# P1.net
KiCad netlist of a schematic drawn in Altium Designer
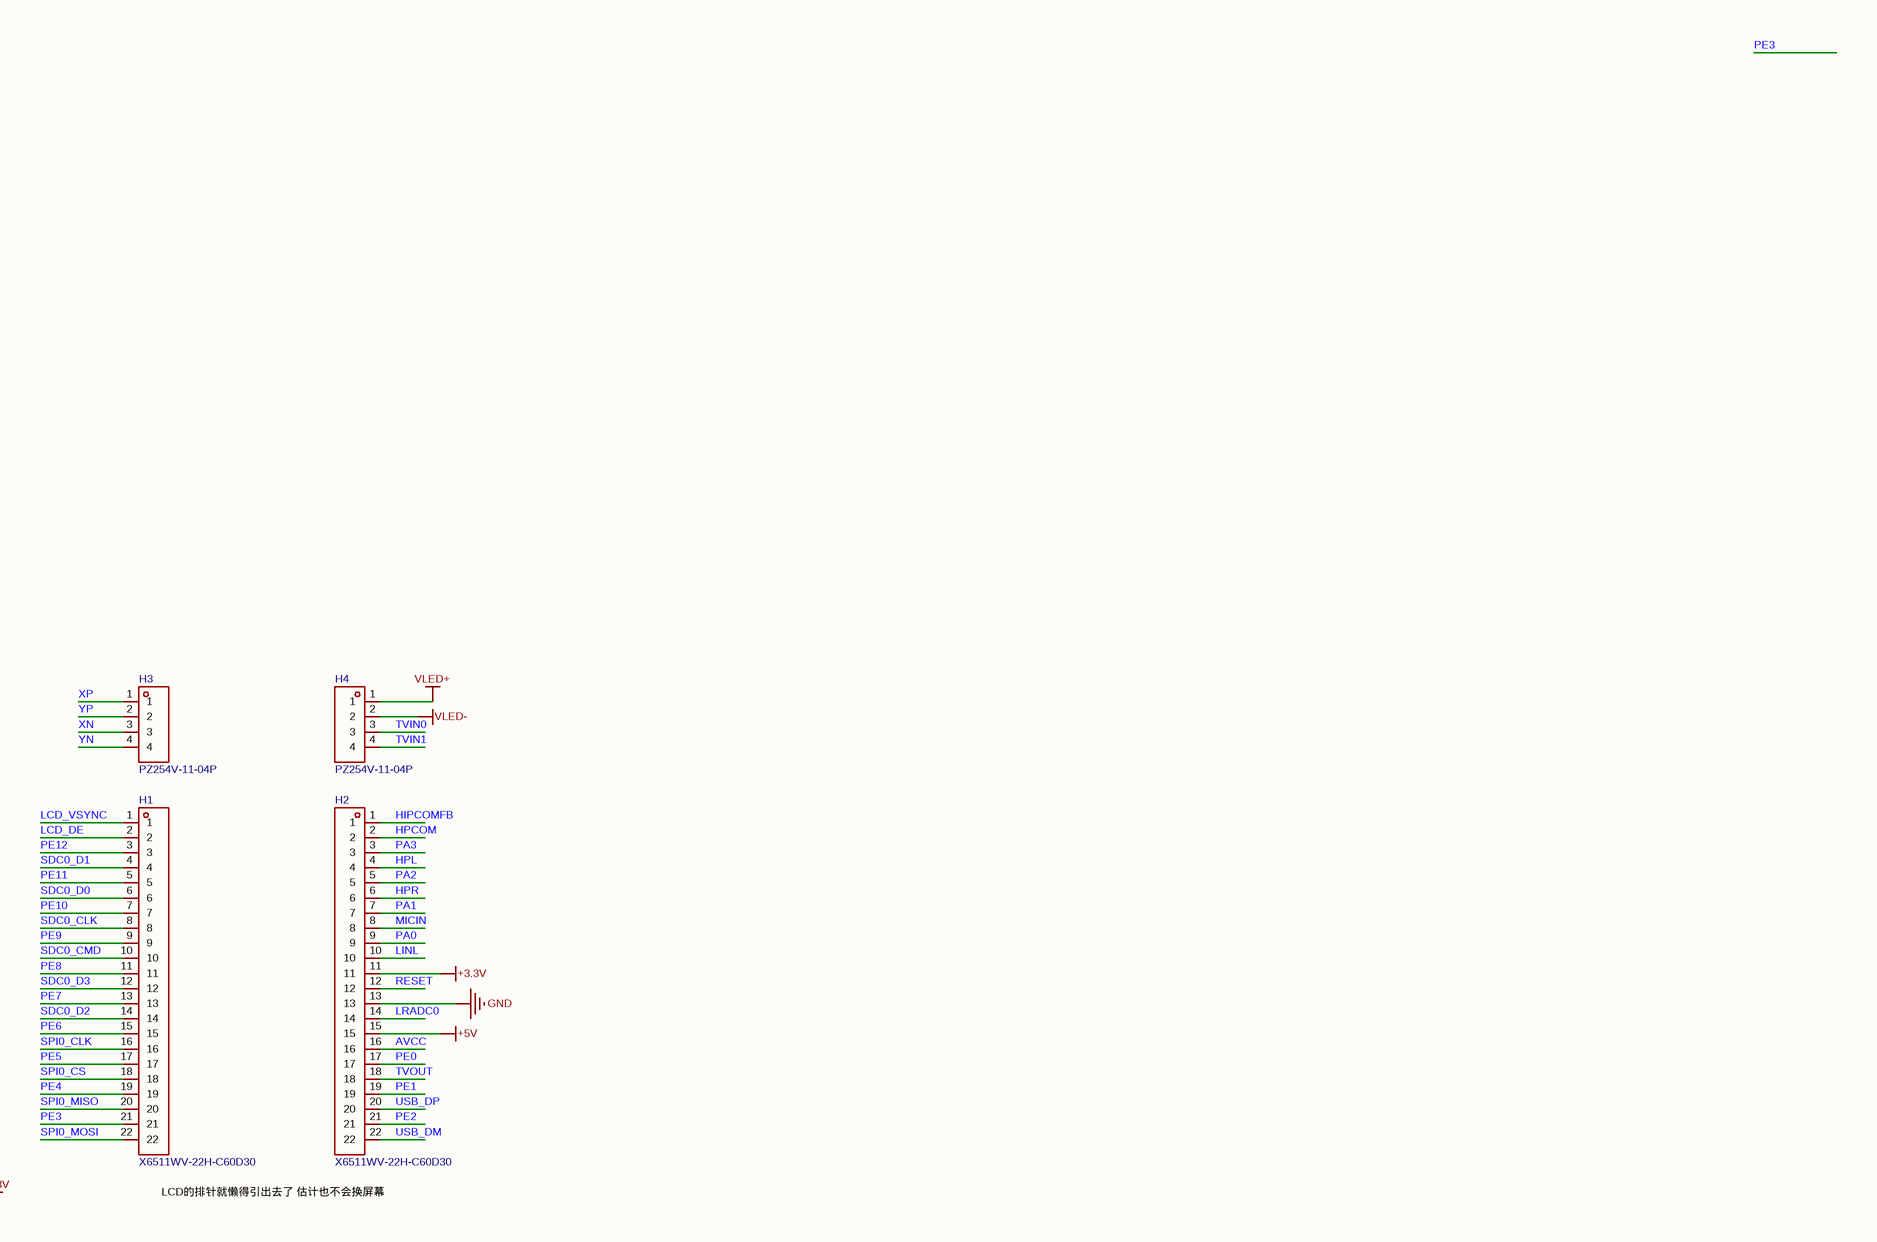
[diagram p0: P1.schdoc, top right]
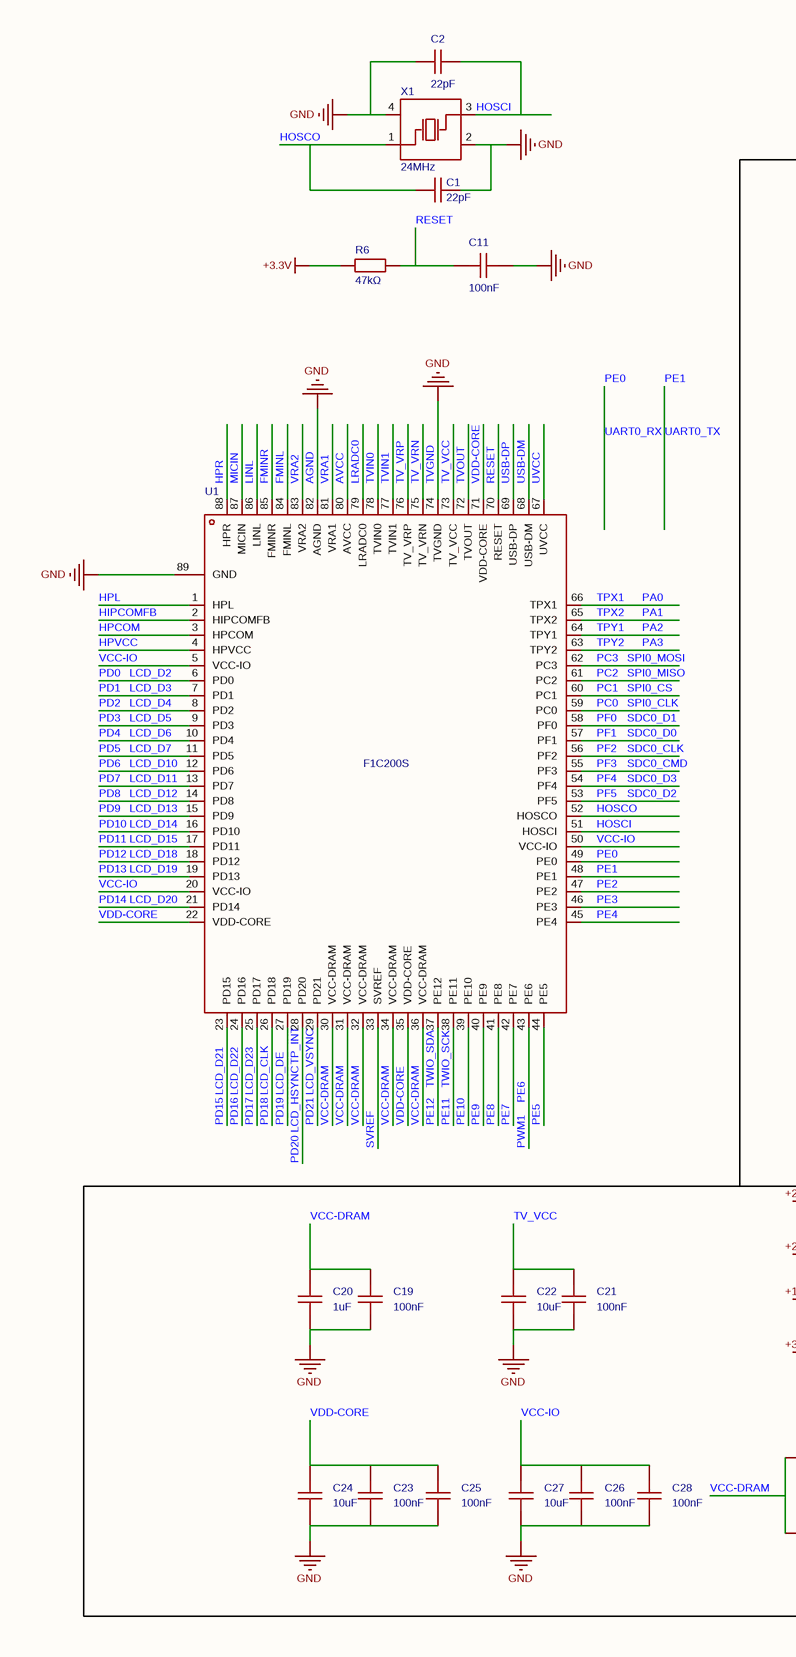
[diagram p1: P1.schdoc, bottom left]
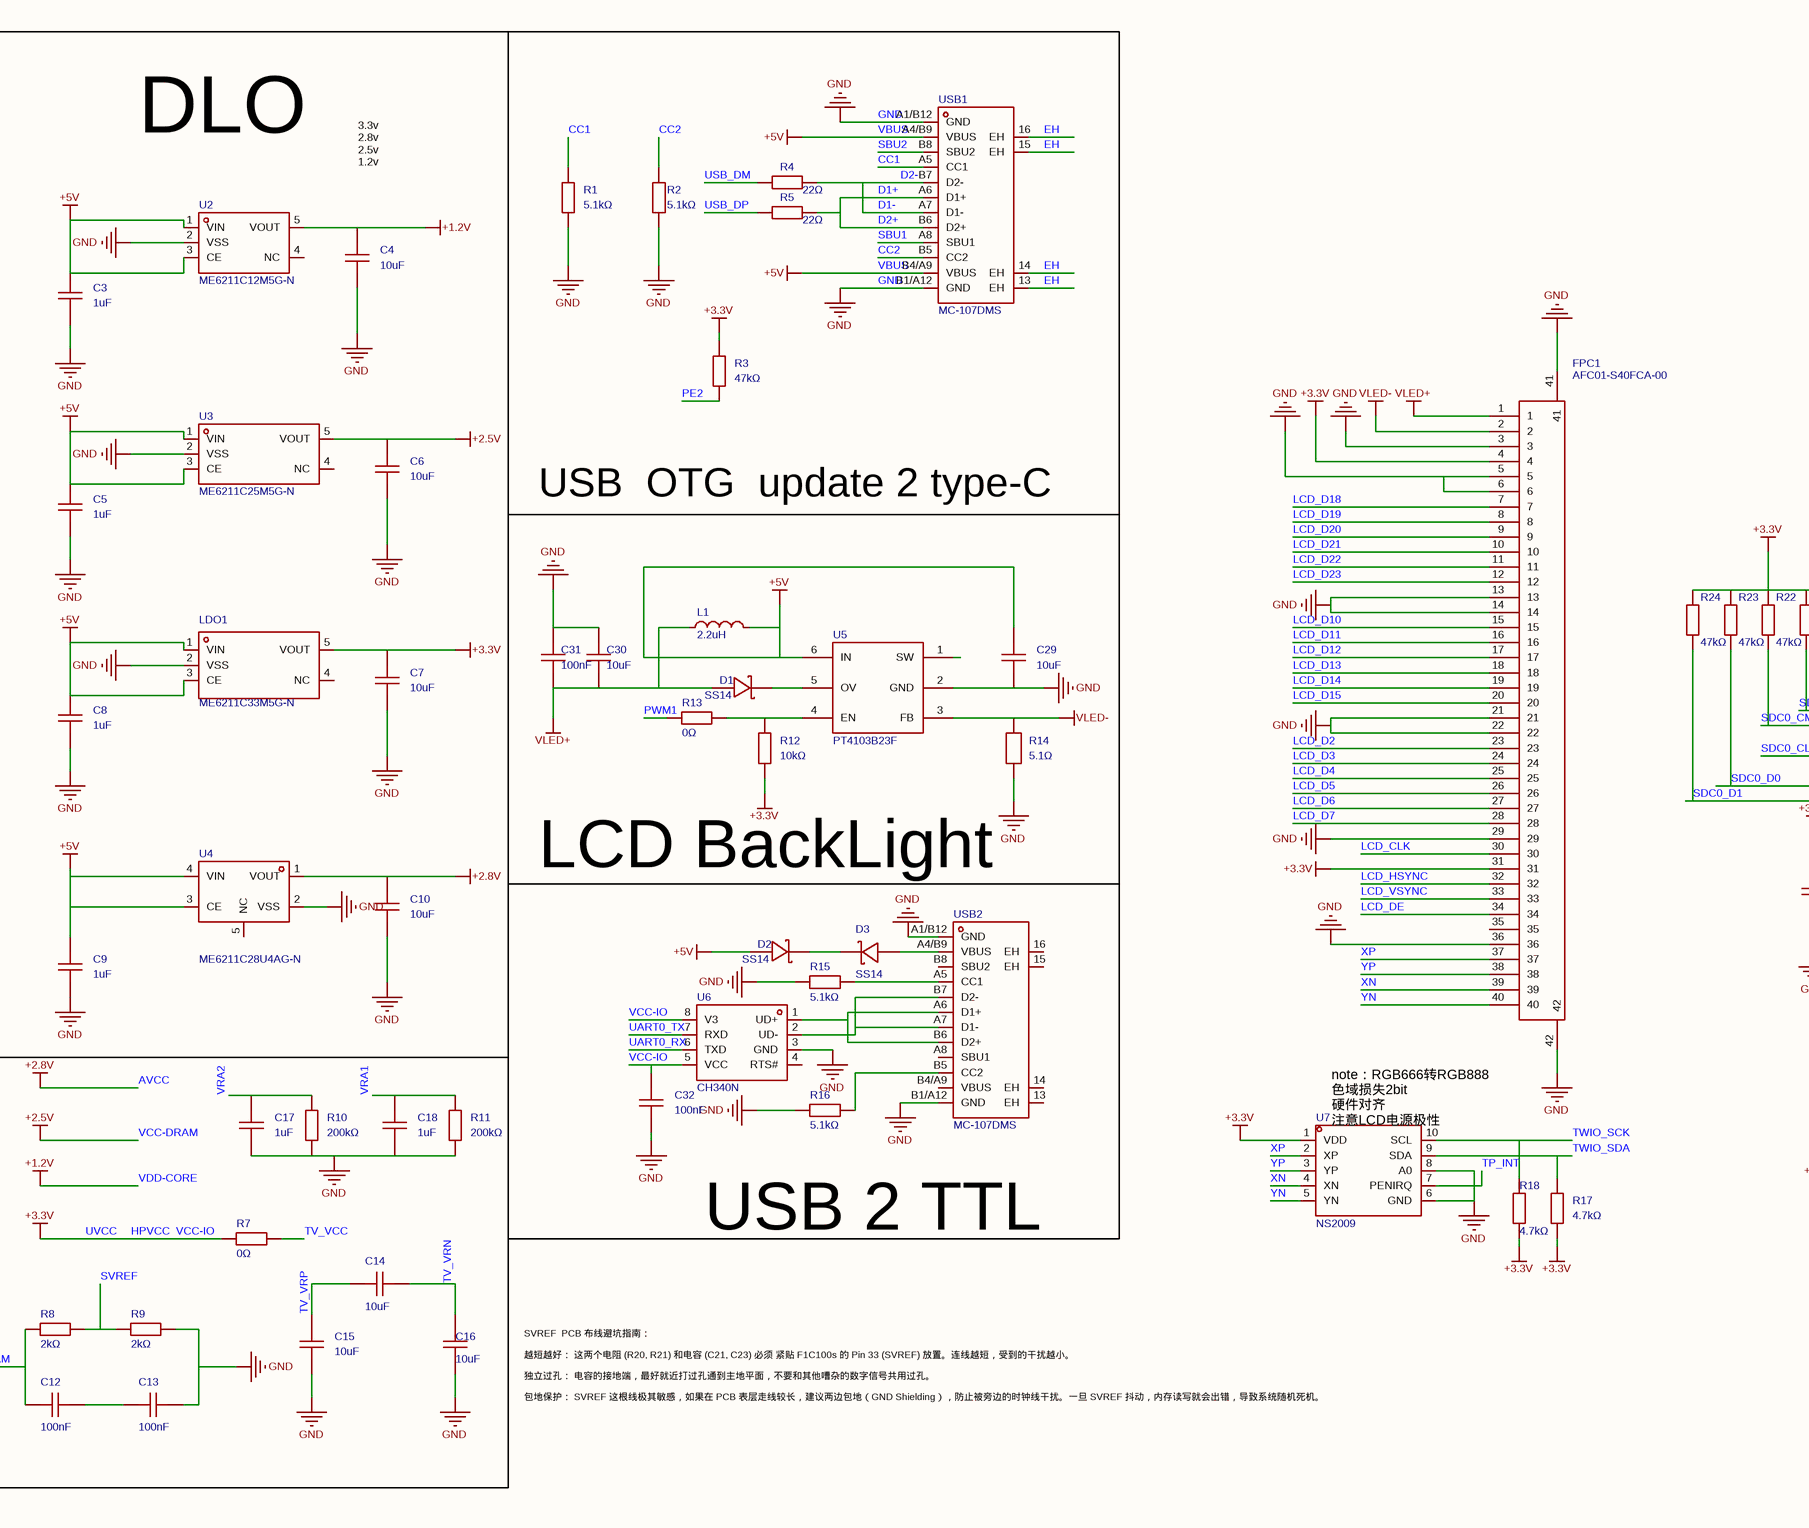
[diagram p2: P1.schdoc, bottom middle]
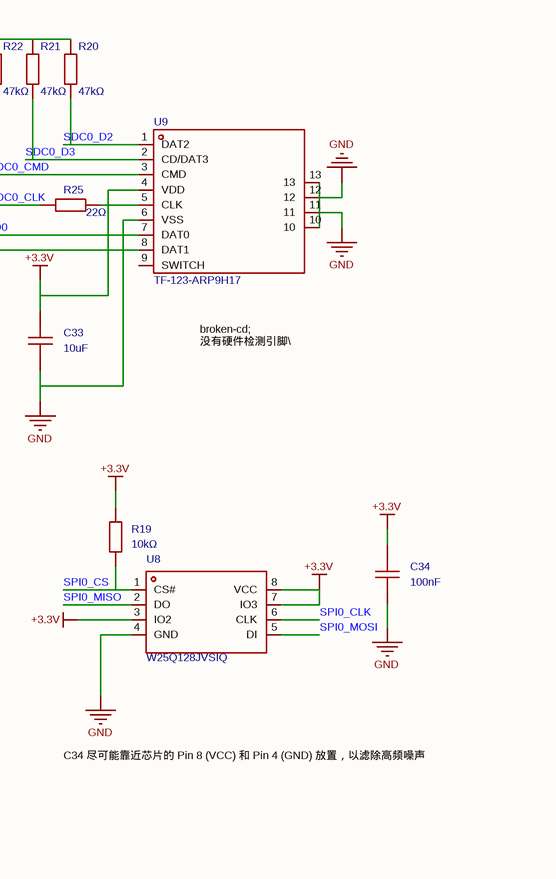
[diagram p3: P1.schdoc, bottom right]

(export (version "E")
  (design (tool "Eeschema 10.0.6"))
  (components
    (comp (ref "C1")
      (value "22pF")
      (footprint "C0603")
      (description "容值:22pF;精度:±5%;额定电压:50V;温度系数:C0G;")
      (fields (field (name "MANUFACTURER") "SAMSUNG(三星)") (field (name "MANUFACTURERPART") "CL10C220JB8NNNC"))
      (libsource (lib "altium-import") (part "root_0_CL10C220JB8NNNC_"))
    )
    (comp (ref "C2")
      (value "22pF")
      (footprint "C0603")
      (description "容值:22pF;精度:±5%;额定电压:50V;温度系数:C0G;")
      (fields (field (name "MANUFACTURER") "SAMSUNG(三星)") (field (name "MANUFACTURERPART") "CL10C220JB8NNNC"))
      (libsource (lib "altium-import") (part "root_0_CL10C220JB8NNNC_"))
    )
    (comp (ref "C3")
      (value "1uF")
      (footprint "C0603")
      (description "容值:1uF;精度:±10%;额定电压:50V;温度系数:X5R;")
      (fields (field (name "MANUFACTURER") "HRE(芯声)") (field (name "MANUFACTURERPART") "CGA0603X5R105K500JT"))
      (libsource (lib "altium-import") (part "root_1_CGA0603X5R105K500JT_"))
    )
    (comp (ref "C4")
      (value "10uF")
      (footprint "C0603")
      (description "容值:10uF;精度:±10%;额定电压:10V;温度系数:X5R;")
      (fields (field (name "MANUFACTURER") "HRE(芯声)") (field (name "MANUFACTURERPART") "CGA0603X5R106K100JT"))
      (libsource (lib "altium-import") (part "root_1_CGA0603X5R106K100JT_"))
    )
    (comp (ref "C5")
      (value "1uF")
      (footprint "C0603")
      (description "容值:1uF;精度:±10%;额定电压:50V;温度系数:X5R;")
      (fields (field (name "MANUFACTURER") "HRE(芯声)") (field (name "MANUFACTURERPART") "CGA0603X5R105K500JT"))
      (libsource (lib "altium-import") (part "root_1_CGA0603X5R105K500JT_"))
    )
    (comp (ref "C6")
      (value "10uF")
      (footprint "C0603")
      (description "容值:10uF;精度:±10%;额定电压:10V;温度系数:X5R;")
      (fields (field (name "MANUFACTURER") "HRE(芯声)") (field (name "MANUFACTURERPART") "CGA0603X5R106K100JT"))
      (libsource (lib "altium-import") (part "root_1_CGA0603X5R106K100JT_"))
    )
    (comp (ref "C7")
      (value "10uF")
      (footprint "C0603")
      (description "容值:10uF;精度:±10%;额定电压:10V;温度系数:X5R;")
      (fields (field (name "MANUFACTURER") "HRE(芯声)") (field (name "MANUFACTURERPART") "CGA0603X5R106K100JT"))
      (libsource (lib "altium-import") (part "root_1_CGA0603X5R106K100JT_"))
    )
    (comp (ref "C8")
      (value "1uF")
      (footprint "C0603")
      (description "容值:1uF;精度:±10%;额定电压:50V;温度系数:X5R;")
      (fields (field (name "MANUFACTURER") "HRE(芯声)") (field (name "MANUFACTURERPART") "CGA0603X5R105K500JT"))
      (libsource (lib "altium-import") (part "root_1_CGA0603X5R105K500JT_"))
    )
    (comp (ref "C9")
      (value "1uF")
      (footprint "C0603")
      (description "容值:1uF;精度:±10%;额定电压:50V;温度系数:X5R;")
      (fields
        (field (name "MANUFACTURER") "HRE(芯声)")
        (field (name "MANUFACTURER PART") "CGA0603X5R105K500JT")
      )
      (libsource (lib "altium-import") (part "root_1_CGA0603X5R105K500JT_"))
    )
    (comp (ref "C10")
      (value "10uF")
      (footprint "C0603")
      (description "容值:10uF;精度:±10%;额定电压:10V;温度系数:X5R;")
      (fields
        (field (name "MANUFACTURER") "HRE(芯声)")
        (field (name "MANUFACTURER PART") "CGA0603X5R106K100JT")
      )
      (libsource (lib "altium-import") (part "root_1_CGA0603X5R106K100JT_"))
    )
    (comp (ref "C11")
      (value "100nF")
      (footprint "C0603")
      (description "容值:100nF;精度:±10%;额定电压:50V;温度系数:X7R;")
      (fields (field (name "MANUFACTURER") "YAGEO(国巨)") (field (name "MANUFACTURERPART") "CC0603KRX7R9BB104"))
      (libsource (lib "altium-import") (part "root_0_CC0603KRX7R9BB104_"))
    )
    (comp (ref "C12")
      (value "100nF")
      (footprint "C0603")
      (description "容值:100nF;精度:±10%;额定电压:50V;温度系数:X7R;")
      (fields (field (name "MANUFACTURER") "YAGEO(国巨)") (field (name "MANUFACTURERPART") "CC0603KRX7R9BB104"))
      (libsource (lib "altium-import") (part "root_0_CC0603KRX7R9BB104_"))
    )
    (comp (ref "C13")
      (value "100nF")
      (footprint "C0603")
      (description "容值:100nF;精度:±10%;额定电压:50V;温度系数:X7R;")
      (fields (field (name "MANUFACTURER") "YAGEO(国巨)") (field (name "MANUFACTURERPART") "CC0603KRX7R9BB104"))
      (libsource (lib "altium-import") (part "root_0_CC0603KRX7R9BB104_"))
    )
    (comp (ref "C14")
      (value "10uF")
      (footprint "C0603")
      (description "容值:10uF;精度:±10%;额定电压:10V;温度系数:X5R;")
      (fields (field (name "MANUFACTURER") "SAMSUNG(三星)") (field (name "MANUFACTURERPART") "CL10A106KP8NNNC"))
      (libsource (lib "altium-import") (part "root_0_CL10A106KP8NNNC_"))
    )
    (comp (ref "C15")
      (value "10uF")
      (footprint "C0603")
      (description "容值:10uF;精度:±10%;额定电压:10V;温度系数:X5R;")
      (fields (field (name "MANUFACTURER") "SAMSUNG(三星)") (field (name "MANUFACTURERPART") "CL10A106KP8NNNC"))
      (libsource (lib "altium-import") (part "root_1_CL10A106KP8NNNC_"))
    )
    (comp (ref "C16")
      (value "10uF")
      (footprint "C0603")
      (description "容值:10uF;精度:±10%;额定电压:10V;温度系数:X5R;")
      (fields (field (name "MANUFACTURER") "SAMSUNG(三星)") (field (name "MANUFACTURERPART") "CL10A106KP8NNNC"))
      (libsource (lib "altium-import") (part "root_1_CL10A106KP8NNNC_"))
    )
    (comp (ref "C17")
      (value "1uF")
      (footprint "C0603")
      (description "容值:1uF;精度:±10%;额定电压:50V;温度系数:X5R;")
      (fields (field (name "MANUFACTURER") "SAMSUNG(三星)") (field (name "MANUFACTURERPART") "CL10A105KB8NNNC"))
      (libsource (lib "altium-import") (part "root_1_CL10A105KB8NNNC_"))
    )
    (comp (ref "C18")
      (value "1uF")
      (footprint "C0603")
      (description "容值:1uF;精度:±10%;额定电压:50V;温度系数:X5R;")
      (fields (field (name "MANUFACTURER") "SAMSUNG(三星)") (field (name "MANUFACTURERPART") "CL10A105KB8NNNC"))
      (libsource (lib "altium-import") (part "root_1_CL10A105KB8NNNC_"))
    )
    (comp (ref "C19")
      (value "100nF")
      (footprint "C0603")
      (description "容值:100nF;精度:±10%;额定电压:50V;温度系数:X7R;")
      (fields (field (name "MANUFACTURER") "YAGEO(国巨)") (field (name "MANUFACTURERPART") "CC0603KRX7R9BB104"))
      (libsource (lib "altium-import") (part "root_1_CC0603KRX7R9BB104_"))
    )
    (comp (ref "C20")
      (value "1uF")
      (footprint "C0603")
      (description "容值:1uF;精度:±10%;额定电压:50V;温度系数:X5R;")
      (fields (field (name "MANUFACTURER") "SAMSUNG(三星)") (field (name "MANUFACTURERPART") "CL10A105KB8NNNC"))
      (libsource (lib "altium-import") (part "root_1_CL10A105KB8NNNC_"))
    )
    (comp (ref "C21")
      (value "100nF")
      (footprint "C0603")
      (description "容值:100nF;精度:±10%;额定电压:50V;温度系数:X7R;")
      (fields (field (name "MANUFACTURER") "YAGEO(国巨)") (field (name "MANUFACTURERPART") "CC0603KRX7R9BB104"))
      (libsource (lib "altium-import") (part "root_1_CC0603KRX7R9BB104_"))
    )
    (comp (ref "C22")
      (value "10uF")
      (footprint "C0603")
      (description "容值:10uF;精度:±10%;额定电压:10V;温度系数:X5R;")
      (fields (field (name "MANUFACTURER") "SAMSUNG(三星)") (field (name "MANUFACTURERPART") "CL10A106KP8NNNC"))
      (libsource (lib "altium-import") (part "root_1_CL10A106KP8NNNC_"))
    )
    (comp (ref "C23")
      (value "100nF")
      (footprint "C0603")
      (description "容值:100nF;精度:±10%;额定电压:50V;温度系数:X7R;")
      (fields (field (name "MANUFACTURER") "YAGEO(国巨)") (field (name "MANUFACTURERPART") "CC0603KRX7R9BB104"))
      (libsource (lib "altium-import") (part "root_1_CC0603KRX7R9BB104_"))
    )
    (comp (ref "C24")
      (value "10uF")
      (footprint "C0603")
      (description "容值:10uF;精度:±10%;额定电压:10V;温度系数:X5R;")
      (fields (field (name "MANUFACTURER") "SAMSUNG(三星)") (field (name "MANUFACTURERPART") "CL10A106KP8NNNC"))
      (libsource (lib "altium-import") (part "root_1_CL10A106KP8NNNC_"))
    )
    (comp (ref "C25")
      (value "100nF")
      (footprint "C0603")
      (description "容值:100nF;精度:±10%;额定电压:50V;温度系数:X7R;")
      (fields (field (name "MANUFACTURER") "YAGEO(国巨)") (field (name "MANUFACTURERPART") "CC0603KRX7R9BB104"))
      (libsource (lib "altium-import") (part "root_1_CC0603KRX7R9BB104_"))
    )
    (comp (ref "C26")
      (value "100nF")
      (footprint "C0603")
      (description "容值:100nF;精度:±10%;额定电压:50V;温度系数:X7R;")
      (fields (field (name "MANUFACTURER") "YAGEO(国巨)") (field (name "MANUFACTURERPART") "CC0603KRX7R9BB104"))
      (libsource (lib "altium-import") (part "root_1_CC0603KRX7R9BB104_"))
    )
    (comp (ref "C27")
      (value "10uF")
      (footprint "C0603")
      (description "容值:10uF;精度:±10%;额定电压:10V;温度系数:X5R;")
      (fields (field (name "MANUFACTURER") "SAMSUNG(三星)") (field (name "MANUFACTURERPART") "CL10A106KP8NNNC"))
      (libsource (lib "altium-import") (part "root_1_CL10A106KP8NNNC_"))
    )
    (comp (ref "C28")
      (value "100nF")
      (footprint "C0603")
      (description "容值:100nF;精度:±10%;额定电压:50V;温度系数:X7R;")
      (fields (field (name "MANUFACTURER") "YAGEO(国巨)") (field (name "MANUFACTURERPART") "CC0603KRX7R9BB104"))
      (libsource (lib "altium-import") (part "root_1_CC0603KRX7R9BB104_"))
    )
    (comp (ref "C29")
      (value "10uF")
      (footprint "C0603")
      (description "容值:10uF;精度:±10%;额定电压:10V;温度系数:X5R;")
      (fields (field (name "MANUFACTURER") "SAMSUNG(三星)") (field (name "MANUFACTURERPART") "CL10A106KP8NNNC"))
      (libsource (lib "altium-import") (part "root_1_CL10A106KP8NNNC_"))
    )
    (comp (ref "C30")
      (value "10uF")
      (footprint "C0603")
      (description "容值:10uF;精度:±20%;额定电压:35V;温度系数:X5R;")
      (fields
        (field (name "MANUFACTURER") "Chinocera(华瓷)")
        (field (name "MANUFACTURERPART") "HGC0603R5106M350NTHJ")
      )
      (libsource (lib "altium-import") (part "root_1_HGC0603R5106M350NTHJ_"))
    )
    (comp (ref "C31")
      (value "100nF")
      (footprint "C0603")
      (description "容值:100nF;精度:±10%;额定电压:50V;温度系数:X7R;")
      (fields (field (name "MANUFACTURER") "HRE(芯声)") (field (name "MANUFACTURERPART") "CGA0603X7R104K500JT"))
      (libsource (lib "altium-import") (part "root_1_CGA0603X7R104K500JT_"))
    )
    (comp (ref "C32")
      (value "100nF")
      (footprint "C0603")
      (description "容值:100nF;精度:±10%;额定电压:50V;温度系数:X7R;")
      (fields
        (field (name "MANUFACTURER") "YAGEO(国巨)")
        (field (name "MANUFACTURER PART") "CC0603KRX7R9BB104")
      )
      (libsource (lib "altium-import") (part "root_1_CC0603KRX7R9BB104_"))
    )
    (comp (ref "C33")
      (value "10uF")
      (footprint "C0603")
      (description "容值:10uF;精度:±10%;额定电压:10V;温度系数:X5R;")
      (fields
        (field (name "MANUFACTURER") "HRE(芯声)")
        (field (name "MANUFACTURER PART") "CGA0603X5R106K100JT")
      )
      (libsource (lib "altium-import") (part "root_3_CGA0603X5R106K100JT_"))
    )
    (comp (ref "C34")
      (value "100nF")
      (footprint "C0603")
      (description "容值:100nF;精度:±10%;额定电压:50V;温度系数:X7R;")
      (fields
        (field (name "MANUFACTURER") "YAGEO(国巨)")
        (field (name "MANUFACTURER PART") "CC0603KRX7R9BB104")
      )
      (libsource (lib "altium-import") (part "root_1_CC0603KRX7R9BB104_"))
    )
    (comp (ref "D1")
      (value "SS14")
      (footprint "SMA_L4.3-W2.6-LS5.2-RD")
      (description "正向压降(Vf):500mV@1A;直流反向耐压(Vr):40V;整流电流:1A;")
      (fields (field (name "MANUFACTURER") "onsemi(安森美)"))
      (libsource (lib "altium-import") (part "root_2_SS14_C83852_"))
    )
    (comp (ref "D2")
      (value "SS14")
      (footprint "SMA_L4.3-W2.6-LS5.2-RD")
      (description "正向压降(Vf):500mV@1A;直流反向耐压(Vr):40V;整流电流:1A;")
      (fields (field (name "MANUFACTURER") "onsemi(安森美)"))
      (libsource (lib "altium-import") (part "root_2_SS14_C83852_"))
    )
    (comp (ref "D3")
      (value "SS14")
      (footprint "SMA_L4.3-W2.6-LS5.2-RD")
      (description "正向压降(Vf):500mV@1A;直流反向耐压(Vr):40V;整流电流:1A;")
      (fields (field (name "MANUFACTURER") "onsemi(安森美)"))
      (libsource (lib "altium-import") (part "root_0_SS14_C83852_"))
    )
    (comp (ref "FPC1")
      (value "AFC01-S40FCA-00")
      (footprint "FPC-SMD_AFC01-S40FCA-00")
      (description "锁定特性:翻盖式;触点类型:下接;触点数量:40P;间距:0.5mm;安装方式:卧贴;工作温度:-45℃~+85℃;")
      (fields (field (name "MANUFACTURER") "JS(钜硕电子)"))
      (libsource (lib "altium-import") (part "root_0_AFC01-S40FCA-00_"))
    )
    (comp (ref "H1")
      (value "X6511WV-22H-C60D30")
      (footprint "HDR-TH_22P-P2.54-V-M")
      (fields (field (name "MANUFACTURER") "XKB Connection(中国星坤)"))
      (libsource (lib "altium-import") (part "root_0_X6511WV-22H-C60D30_"))
    )
    (comp (ref "H2")
      (value "X6511WV-22H-C60D30")
      (footprint "HDR-TH_22P-P2.54-V-M")
      (fields (field (name "MANUFACTURER") "XKB Connection(中国星坤)"))
      (libsource (lib "altium-import") (part "root_0_mirrored_X6511WV-22H-C60D30_"))
    )
    (comp (ref "H3")
      (value "PZ254V-11-04P")
      (footprint "HDR-TH_4P-P2.54-V-M")
      (fields (field (name "MANUFACTURER") "XFCN(兴飞)"))
      (libsource (lib "altium-import") (part "root_0_PZ254V-11-04P_"))
    )
    (comp (ref "H4")
      (value "PZ254V-11-04P")
      (footprint "HDR-TH_4P-P2.54-V-M")
      (fields (field (name "MANUFACTURER") "XFCN(兴飞)"))
      (libsource (lib "altium-import") (part "root_0_mirrored_PZ254V-11-04P_"))
    )
    (comp (ref "L1")
      (value "2.2uH")
      (footprint "IND-SMD_L2.5-W2.0_MHCHL2520")
      (description "电感值:2.2uH;精度:±20%;额定电流:3A;饱和电流(Isat):3.8A;类型:一体成型电感;")
      (fields
        (field (name "MANUFACTURER") "cjiang(长江微电)")
        (field (name "MANUFACTURERPART") "FTC252012S2R2MBCA")
      )
      (libsource (lib "altium-import") (part "root_0_FTC252012S2R2MBCA_"))
    )
    (comp (ref "LDO1")
      (value "ME6211C33M5G-N")
      (footprint "SOT-23-5_L3.0-W1.7-P0.95-LS2.8-BL")
      (description "输出类型:固定;工作电压:6V;输出电压:3.3V;输出电流:500mA;电源纹波抑制比(PSRR):70dB@(1kHz);输出极性:正极;")
      (fields (field (name "MANUFACTURER") "MICRONE(南京微盟)"))
      (libsource (lib "altium-import") (part "root_0_ME6211C33M5G-N_"))
    )
    (comp (ref "R1")
      (value "5.1kΩ")
      (footprint "R0603")
      (description "电阻类型:厚膜电阻;阻值:5.1kΩ;精度:±1%;功率:100mW;工作电压:75V;温度系数:±100ppm/℃;")
      (fields
        (field (name "MANUFACTURER") "UNI-ROYAL(厚声)")
        (field (name "MANUFACTURERPART") "0603WAF5101T5E")
      )
      (libsource (lib "altium-import") (part "root_1_0603WAF5101T5E_"))
    )
    (comp (ref "R2")
      (value "5.1kΩ")
      (footprint "R0603")
      (description "电阻类型:厚膜电阻;阻值:5.1kΩ;精度:±1%;功率:100mW;工作电压:75V;温度系数:±100ppm/℃;")
      (fields
        (field (name "MANUFACTURER") "UNI-ROYAL(厚声)")
        (field (name "MANUFACTURERPART") "0603WAF5101T5E")
      )
      (libsource (lib "altium-import") (part "root_1_0603WAF5101T5E_"))
    )
    (comp (ref "R3")
      (value "47kΩ")
      (footprint "R0603")
      (description "电阻类型:厚膜电阻;阻值:47kΩ;精度:±1%;功率:100mW;工作电压:75V;温度系数:±100ppm/℃;")
      (fields
        (field (name "MANUFACTURER") "UNI-ROYAL(厚声)")
        (field (name "MANUFACTURERPART") "0603WAF4702T5E")
      )
      (libsource (lib "altium-import") (part "root_1_0603WAF4702T5E_"))
    )
    (comp (ref "R4")
      (value "22Ω")
      (footprint "R0603")
      (description "电阻类型:厚膜电阻;阻值:22Ω;精度:±1%;功率:100mW;最大工作电压:75V;温度系数:±100ppm/℃;")
      (fields
        (field (name "MANUFACTURER") "UNI-ROYAL(厚声)")
        (field (name "MANUFACTURERPART") "0603WAF220JT5E")
      )
      (libsource (lib "altium-import") (part "root_0_0603WAF220JT5E_"))
    )
    (comp (ref "R5")
      (value "22Ω")
      (footprint "R0603")
      (description "电阻类型:厚膜电阻;阻值:22Ω;精度:±1%;功率:100mW;最大工作电压:75V;温度系数:±100ppm/℃;")
      (fields
        (field (name "MANUFACTURER") "UNI-ROYAL(厚声)")
        (field (name "MANUFACTURERPART") "0603WAF220JT5E")
      )
      (libsource (lib "altium-import") (part "root_0_0603WAF220JT5E_"))
    )
    (comp (ref "R6")
      (value "47kΩ")
      (footprint "R0603")
      (description "电阻类型:厚膜电阻;阻值:47kΩ;精度:±1%;功率:100mW;工作电压:75V;温度系数:±100ppm/℃;")
      (fields
        (field (name "MANUFACTURER") "UNI-ROYAL(厚声)")
        (field (name "MANUFACTURER PART") "0603WAF4702T5E")
      )
      (libsource (lib "altium-import") (part "root_0_0603WAF4702T5E_"))
    )
    (comp (ref "R7")
      (value "0Ω")
      (footprint "R0603")
      (description "电阻类型:厚膜电阻;阻值:0Ω;精度:±1%;功率:100mW;工作电压:75V;温度系数:-;")
      (fields
        (field (name "MANUFACTURER") "UNI-ROYAL(厚声)")
        (field (name "MANUFACTURERPART") "0603WAF0000T5E")
      )
      (libsource (lib "altium-import") (part "root_0_0603WAF0000T5E_"))
    )
    (comp (ref "R8")
      (value "2kΩ")
      (footprint "R0603")
      (description "电阻类型:厚膜电阻;阻值:2kΩ;精度:±1%;功率:100mW;工作电压:75V;温度系数:±100ppm/℃;")
      (fields
        (field (name "MANUFACTURER") "UNI-ROYAL(厚声)")
        (field (name "MANUFACTURERPART") "0603WAF2001T5E")
      )
      (libsource (lib "altium-import") (part "root_0_0603WAF2001T5E_"))
    )
    (comp (ref "R9")
      (value "2kΩ")
      (footprint "R0603")
      (description "电阻类型:厚膜电阻;阻值:2kΩ;精度:±1%;功率:100mW;工作电压:75V;温度系数:±100ppm/℃;")
      (fields
        (field (name "MANUFACTURER") "UNI-ROYAL(厚声)")
        (field (name "MANUFACTURERPART") "0603WAF2001T5E")
      )
      (libsource (lib "altium-import") (part "root_0_0603WAF2001T5E_"))
    )
    (comp (ref "R10")
      (value "200kΩ")
      (footprint "R0603")
      (description "电阻类型:厚膜电阻;阻值:200kΩ;精度:±1%;功率:100mW;最大工作电压:75V;温度系数:±100ppm/℃;")
      (fields
        (field (name "MANUFACTURER") "UNI-ROYAL(厚声)")
        (field (name "MANUFACTURERPART") "0603WAF2003T5E")
      )
      (libsource (lib "altium-import") (part "root_1_0603WAF2003T5E_"))
    )
    (comp (ref "R11")
      (value "200kΩ")
      (footprint "R0603")
      (description "电阻类型:厚膜电阻;阻值:200kΩ;精度:±1%;功率:100mW;最大工作电压:75V;温度系数:±100ppm/℃;")
      (fields
        (field (name "MANUFACTURER") "UNI-ROYAL(厚声)")
        (field (name "MANUFACTURERPART") "0603WAF2003T5E")
      )
      (libsource (lib "altium-import") (part "root_1_0603WAF2003T5E_"))
    )
    (comp (ref "R12")
      (value "10kΩ")
      (footprint "R0603")
      (description "电阻类型:厚膜电阻;阻值:10kΩ;精度:±1%;功率:100mW;工作电压:75V;温度系数:±100ppm/℃;")
      (fields
        (field (name "MANUFACTURER") "UNI-ROYAL(厚声)")
        (field (name "MANUFACTURERPART") "0603WAF1002T5E")
      )
      (libsource (lib "altium-import") (part "root_1_0603WAF1002T5E_"))
    )
    (comp (ref "R13")
      (value "0Ω")
      (footprint "R0603")
      (description "电阻类型:厚膜电阻;阻值:0Ω;精度:±1%;功率:100mW;工作电压:75V;温度系数:-;")
      (fields
        (field (name "MANUFACTURER") "UNI-ROYAL(厚声)")
        (field (name "MANUFACTURERPART") "0603WAF0000T5E")
      )
      (libsource (lib "altium-import") (part "root_0_0603WAF0000T5E_"))
    )
    (comp (ref "R14")
      (value "5.1Ω")
      (footprint "R0603")
      (description "电阻类型:厚膜电阻;阻值:5.1Ω;精度:±1%;功率:100mW;工作电压:75V;温度系数:±200ppm/℃;")
      (fields (field (name "MANUFACTURER") "FOJAN(富捷)") (field (name "MANUFACTURERPART") "FRC0603F5R10TS"))
      (libsource (lib "altium-import") (part "root_1_FRC0603F5R10TS_"))
    )
    (comp (ref "R15")
      (value "5.1kΩ")
      (footprint "R0603")
      (description "电阻类型:厚膜电阻;阻值:5.1kΩ;精度:±1%;功率:100mW;工作电压:75V;温度系数:±100ppm/℃;")
      (fields
        (field (name "MANUFACTURER") "UNI-ROYAL(厚声)")
        (field (name "MANUFACTURER PART") "0603WAF5101T5E")
      )
      (libsource (lib "altium-import") (part "root_0_0603WAF5101T5E_"))
    )
    (comp (ref "R16")
      (value "5.1kΩ")
      (footprint "R0603")
      (description "电阻类型:厚膜电阻;阻值:5.1kΩ;精度:±1%;功率:100mW;工作电压:75V;温度系数:±100ppm/℃;")
      (fields
        (field (name "MANUFACTURER") "UNI-ROYAL(厚声)")
        (field (name "MANUFACTURER PART") "0603WAF5101T5E")
      )
      (libsource (lib "altium-import") (part "root_0_0603WAF5101T5E_"))
    )
    (comp (ref "R17")
      (value "4.7kΩ")
      (footprint "R0603")
      (description "电阻类型:厚膜电阻;阻值:4.7kΩ;精度:±1%;功率:100mW;工作电压:75V;温度系数:±100ppm/℃;")
      (fields
        (field (name "MANUFACTURER") "UNI-ROYAL(厚声)")
        (field (name "MANUFACTURERPART") "0603WAF4701T5E")
      )
      (libsource (lib "altium-import") (part "root_1_0603WAF4701T5E_"))
    )
    (comp (ref "R18")
      (value "4.7kΩ")
      (footprint "R0603")
      (description "电阻类型:厚膜电阻;阻值:4.7kΩ;精度:±1%;功率:100mW;工作电压:75V;温度系数:±100ppm/℃;")
      (fields
        (field (name "MANUFACTURER") "UNI-ROYAL(厚声)")
        (field (name "MANUFACTURERPART") "0603WAF4701T5E")
      )
      (libsource (lib "altium-import") (part "root_1_0603WAF4701T5E_"))
    )
    (comp (ref "R19")
      (value "10kΩ")
      (footprint "R0603")
      (description "电阻类型:厚膜电阻;阻值:10kΩ;精度:±1%;功率:100mW;工作电压:75V;温度系数:±100ppm/℃;")
      (fields
        (field (name "MANUFACTURER") "UNI-ROYAL(厚声)")
        (field (name "MANUFACTURER PART") "0603WAF1002T5E")
      )
      (libsource (lib "altium-import") (part "root_1_0603WAF1002T5E_"))
    )
    (comp (ref "R20")
      (value "47kΩ")
      (footprint "R0603")
      (description "电阻类型:厚膜电阻;阻值:47kΩ;精度:±1%;功率:100mW;工作电压:75V;温度系数:±100ppm/℃;")
      (fields
        (field (name "MANUFACTURER") "UNI-ROYAL(厚声)")
        (field (name "MANUFACTURER PART") "0603WAF4702T5E")
      )
      (libsource (lib "altium-import") (part "root_1_0603WAF4702T5E_"))
    )
    (comp (ref "R21")
      (value "47kΩ")
      (footprint "R0603")
      (description "电阻类型:厚膜电阻;阻值:47kΩ;精度:±1%;功率:100mW;工作电压:75V;温度系数:±100ppm/℃;")
      (fields
        (field (name "MANUFACTURER") "UNI-ROYAL(厚声)")
        (field (name "MANUFACTURER PART") "0603WAF4702T5E")
      )
      (libsource (lib "altium-import") (part "root_1_0603WAF4702T5E_"))
    )
    (comp (ref "R22")
      (value "47kΩ")
      (footprint "R0603")
      (description "电阻类型:厚膜电阻;阻值:47kΩ;精度:±1%;功率:100mW;工作电压:75V;温度系数:±100ppm/℃;")
      (fields
        (field (name "MANUFACTURER") "UNI-ROYAL(厚声)")
        (field (name "MANUFACTURER PART") "0603WAF4702T5E")
      )
      (libsource (lib "altium-import") (part "root_1_0603WAF4702T5E_"))
    )
    (comp (ref "R23")
      (value "47kΩ")
      (footprint "R0603")
      (description "电阻类型:厚膜电阻;阻值:47kΩ;精度:±1%;功率:100mW;工作电压:75V;温度系数:±100ppm/℃;")
      (fields
        (field (name "MANUFACTURER") "UNI-ROYAL(厚声)")
        (field (name "MANUFACTURER PART") "0603WAF4702T5E")
      )
      (libsource (lib "altium-import") (part "root_1_0603WAF4702T5E_"))
    )
    (comp (ref "R24")
      (value "47kΩ")
      (footprint "R0603")
      (description "电阻类型:厚膜电阻;阻值:47kΩ;精度:±1%;功率:100mW;工作电压:75V;温度系数:±100ppm/℃;")
      (fields
        (field (name "MANUFACTURER") "UNI-ROYAL(厚声)")
        (field (name "MANUFACTURER PART") "0603WAF4702T5E")
      )
      (libsource (lib "altium-import") (part "root_1_0603WAF4702T5E_"))
    )
    (comp (ref "R25")
      (value "22Ω")
      (footprint "R0603")
      (description "电阻类型:厚膜电阻;阻值:22Ω;精度:±1%;功率:100mW;最大工作电压:75V;温度系数:±100ppm/℃;")
      (fields
        (field (name "MANUFACTURER") "UNI-ROYAL(厚声)")
        (field (name "MANUFACTURER PART") "0603WAF220JT5E")
      )
      (libsource (lib "altium-import") (part "root_0_0603WAF220JT5E_"))
    )
    (comp (ref "U1")
      (value "F1C200S")
      (footprint "QFN-88_L10.0-W10.0-P0.40-BL-EP6.75")
      (description "CPU内核:-;")
      (fields (field (name "MANUFACTURER") "Allwinner(全志)"))
      (libsource (lib "altium-import") (part "root_0_F1C200S_"))
    )
    (comp (ref "U2")
      (value "ME6211C12M5G-N")
      (footprint "SOT-23-5_L3.0-W1.7-P0.95-LS2.8-BL")
      (description "输出类型:固定;工作电压:6V;输出电压:1.2V;输出电流:300mA;电源纹波抑制比(PSRR):70dB@(1kHz);输出极性:正极;")
      (fields (field (name "MANUFACTURER") "MICRONE(南京微盟)"))
      (libsource (lib "altium-import") (part "root_0_ME6211C12M5G-N_"))
    )
    (comp (ref "U3")
      (value "ME6211C25M5G-N")
      (footprint "SOT-23-5_L3.0-W1.7-P0.95-LS2.8-BR")
      (description "输出类型:固定;工作电压:6V;输出电压:2.5V;输出电流:400mA;电源纹波抑制比(PSRR):62dB@(10kHz);输出极性:正极;")
      (fields (field (name "MANUFACTURER") "MICRONE(南京微盟)"))
      (libsource (lib "altium-import") (part "root_0_ME6211C25M5G-N_"))
    )
    (comp (ref "U4")
      (value "ME6211C28U4AG-N")
      (footprint "FBP4L_L1.0-W1.0-P0.65-BL-EP")
      (description "输出类型:固定;工作电压:6V;输出电压:2.8V;输出电流:450mA;电源纹波抑制比(PSRR):62dB@(10kHz);输出极性:正极;")
      (fields (field (name "MANUFACTURER") "MICRONE(南京微盟)"))
      (libsource (lib "altium-import") (part "root_0_mirrored_ME6211C28U4AG-N_"))
    )
    (comp (ref "U5")
      (value "PT4103B23F")
      (footprint "SOT-23-6_L2.9-W1.6-P0.95-LS2.8-BR")
      (description "类型:DC-DC;工作电压(DC):2.5V~6V;开关频率:1MHz~1.5MHz;通道数:1;调光:PWM；模拟;拓扑结构:升压;")
      (fields (field (name "MANUFACTURER") "PowTech(华润矽威)"))
      (libsource (lib "altium-import") (part "root_0_mirrored_PT4103B23F_"))
    )
    (comp (ref "U6")
      (value "CH340N")
      (footprint "SOP-8_L4.9-W3.9-P1.27-LS6.0-BL")
      (description "应用功能:USB转串口;USB协议版本:USB 2.0;通道数:1;数据速率:2Mbps;")
      (fields (field (name "MANUFACTURER") "WCH(南京沁恒)"))
      (libsource (lib "altium-import") (part "root_0_mirrored_CH340N_"))
    )
    (comp (ref "U7")
      (value "NS2009")
      (footprint "MSOP-10_L3.0-W3.0-P0.50-LS5.0-BL")
      (description "分辨率:12位;接口类型:I2C;工作电压:2V~5.5V;")
      (fields (field (name "MANUFACTURER") "Nsiway(纳芯威)"))
      (libsource (lib "altium-import") (part "root_0_NS2009_"))
    )
    (comp (ref "U8")
      (value "W25Q128JVSIQ")
      (footprint "SOIC-8_L5.3-W5.3-P1.27-LS8.0-BL")
      (description "接口类型:SPI;存储容量:128Mbit;时钟频率(fc):133MHz;")
      (fields (field (name "MANUFACTURER") "Winbond(华邦)"))
      (libsource (lib "altium-import") (part "root_0_W25Q128JVSIQ_"))
    )
    (comp (ref "U9")
      (value "TF-123-ARP9H17")
      (footprint "TF-SMD_TF-123-ARP9H15")
      (description "卡连接方式:拔插式;卡类型:MicroSD卡(TF卡);连接器类型:卡座;本体最大高度:1.7mm;工作温度:-25℃~+85℃;")
      (fields (field (name "MANUFACTURER") "XUNPU(讯普)"))
      (libsource (lib "altium-import") (part "root_0_TF-123-ARP9H17_"))
    )
    (comp (ref "USB1")
      (value "MC-107DMS")
      (footprint "USB-C-SMD_MC-107DMS")
      (description "连接器类型:Type-C;协议标准:USB 3.1;公母:母;安装方式:卧贴;触点数量:16P;端口数量:1;额定电流 - 电源:5A;工作温度:-40℃~+85℃;")
      (fields (field (name "MANUFACTURER") "HANBO(汉博)"))
      (libsource (lib "altium-import") (part "root_0_MC-107DMS_"))
    )
    (comp (ref "USB2")
      (value "MC-107DMS")
      (footprint "USB-C-SMD_MC-107DMS")
      (description "连接器类型:Type-C;协议标准:USB 3.1;公母:母;安装方式:卧贴;触点数量:16P;端口数量:1;额定电流 - 电源:5A;工作温度:-40℃~+85℃;")
      (fields (field (name "MANUFACTURER") "HANBO(汉博)"))
      (libsource (lib "altium-import") (part "root_0_MC-107DMS_"))
    )
    (comp (ref "X1")
      (value "24MHz")
      (footprint "CRYSTAL-SMD_4P-L2.5-W2.0-BL")
      (description "晶振类型:贴片晶振;频率:24MHz;常温频差:±10ppm;负载电容:18pF;频率稳定度:±20ppm;")
      (fields (field (name "MANUFACTURER") "YXC(扬兴晶振)") (field (name "MANUFACTURERPART") "X252024MRB4SI"))
      (libsource (lib "altium-import") (part "root_0_X252024MRB4SI_"))
    )
  )
  (nets
    (net (code "1") (name "+1.2V") (class "Default")
      (node (ref "C23") (pin "2") (pinfunction "2_2") (pintype "passive"))
      (node (ref "C24") (pin "2") (pinfunction "2_2") (pintype "passive"))
      (node (ref "C25") (pin "2") (pinfunction "2_2") (pintype "passive"))
      (node (ref "C4") (pin "2") (pinfunction "2_2") (pintype "passive"))
      (node (ref "U1") (pin "22") (pinfunction "VDD-CORE_22") (pintype "passive"))
      (node (ref "U1") (pin "35") (pinfunction "VDD-CORE_35") (pintype "passive"))
      (node (ref "U1") (pin "71") (pinfunction "VDD-CORE_71") (pintype "passive"))
      (node (ref "U2") (pin "5") (pinfunction "VOUT_5") (pintype "passive"))
    )
    (net (code "2") (name "+2.5V") (class "Default")
      (node (ref "C12") (pin "1") (pinfunction "1_1") (pintype "passive"))
      (node (ref "C19") (pin "2") (pinfunction "2_2") (pintype "passive"))
      (node (ref "C20") (pin "2") (pinfunction "2_2") (pintype "passive"))
      (node (ref "C6") (pin "2") (pinfunction "2_2") (pintype "passive"))
      (node (ref "R8") (pin "1") (pinfunction "1_1") (pintype "passive"))
      (node (ref "U1") (pin "30") (pinfunction "VCC-DRAM_30") (pintype "passive"))
      (node (ref "U1") (pin "31") (pinfunction "VCC-DRAM_31") (pintype "passive"))
      (node (ref "U1") (pin "32") (pinfunction "VCC-DRAM_32") (pintype "passive"))
      (node (ref "U1") (pin "34") (pinfunction "VCC-DRAM_34") (pintype "passive"))
      (node (ref "U1") (pin "36") (pinfunction "VCC-DRAM_36") (pintype "passive"))
      (node (ref "U3") (pin "5") (pinfunction "VOUT_5") (pintype "passive"))
    )
    (net (code "3") (name "+2.8V") (class "Default")
      (node (ref "C10") (pin "2") (pinfunction "2_2") (pintype "passive"))
      (node (ref "H2") (pin "16") (pinfunction "16_16") (pintype "passive"))
      (node (ref "U1") (pin "80") (pinfunction "AVCC_80") (pintype "passive"))
      (node (ref "U4") (pin "1") (pinfunction "VOUT_1") (pintype "passive"))
    )
    (net (code "4") (name "+3.3V") (class "Default")
      (node (ref "C26") (pin "2") (pinfunction "2_2") (pintype "passive"))
      (node (ref "C27") (pin "2") (pinfunction "2_2") (pintype "passive"))
      (node (ref "C28") (pin "2") (pinfunction "2_2") (pintype "passive"))
      (node (ref "C32") (pin "2") (pinfunction "2_2") (pintype "passive"))
      (node (ref "C33") (pin "1") (pinfunction "1_1") (pintype "passive"))
      (node (ref "C34") (pin "2") (pinfunction "2_2") (pintype "passive"))
      (node (ref "C7") (pin "2") (pinfunction "2_2") (pintype "passive"))
      (node (ref "FPC1") (pin "31") (pinfunction "31_31") (pintype "passive"))
      (node (ref "FPC1") (pin "4") (pinfunction "4_4") (pintype "passive"))
      (node (ref "H2") (pin "11") (pinfunction "11_11") (pintype "passive"))
      (node (ref "LDO1") (pin "5") (pinfunction "VOUT_5") (pintype "passive"))
      (node (ref "R12") (pin "1") (pinfunction "1_1") (pintype "passive"))
      (node (ref "R17") (pin "1") (pinfunction "1_1") (pintype "passive"))
      (node (ref "R18") (pin "1") (pinfunction "1_1") (pintype "passive"))
      (node (ref "R19") (pin "2") (pinfunction "2_2") (pintype "passive"))
      (node (ref "R20") (pin "2") (pinfunction "2_2") (pintype "passive"))
      (node (ref "R21") (pin "2") (pinfunction "2_2") (pintype "passive"))
      (node (ref "R22") (pin "2") (pinfunction "2_2") (pintype "passive"))
      (node (ref "R23") (pin "2") (pinfunction "2_2") (pintype "passive"))
      (node (ref "R24") (pin "2") (pinfunction "2_2") (pintype "passive"))
      (node (ref "R3") (pin "2") (pinfunction "2_2") (pintype "passive"))
      (node (ref "R6") (pin "1") (pinfunction "1_1") (pintype "passive"))
      (node (ref "R7") (pin "1") (pinfunction "1_1") (pintype "passive"))
      (node (ref "U1") (pin "20") (pinfunction "VCC-IO_20") (pintype "passive"))
      (node (ref "U1") (pin "4") (pinfunction "HPVCC_4") (pintype "passive"))
      (node (ref "U1") (pin "5") (pinfunction "VCC-IO_5") (pintype "passive"))
      (node (ref "U1") (pin "50") (pinfunction "VCC-IO_50") (pintype "passive"))
      (node (ref "U1") (pin "67") (pinfunction "UVCC_67") (pintype "passive"))
      (node (ref "U6") (pin "5") (pinfunction "VCC_5") (pintype "passive"))
      (node (ref "U6") (pin "8") (pinfunction "V3_8") (pintype "passive"))
      (node (ref "U7") (pin "1") (pinfunction "VDD_1") (pintype "passive"))
      (node (ref "U8") (pin "3") (pinfunction "IO2_3") (pintype "passive"))
      (node (ref "U8") (pin "7") (pinfunction "IO3_7") (pintype "passive"))
      (node (ref "U8") (pin "8") (pinfunction "VCC_8") (pintype "passive"))
      (node (ref "U9") (pin "4") (pinfunction "VDD_4") (pintype "passive"))
    )
    (net (code "5") (name "+5V") (class "Default")
      (node (ref "C29") (pin "2") (pinfunction "2_2") (pintype "passive"))
      (node (ref "C3") (pin "2") (pinfunction "2_2") (pintype "passive"))
      (node (ref "C5") (pin "2") (pinfunction "2_2") (pintype "passive"))
      (node (ref "C8") (pin "2") (pinfunction "2_2") (pintype "passive"))
      (node (ref "C9") (pin "2") (pinfunction "2_2") (pintype "passive"))
      (node (ref "D2") (pin "2") (pinfunction "A_2") (pintype "passive"))
      (node (ref "H2") (pin "15") (pinfunction "15_15") (pintype "passive"))
      (node (ref "L1") (pin "2") (pinfunction "2_2") (pintype "passive"))
      (node (ref "LDO1") (pin "1") (pinfunction "VIN_1") (pintype "passive"))
      (node (ref "LDO1") (pin "3") (pinfunction "CE_3") (pintype "passive"))
      (node (ref "U2") (pin "1") (pinfunction "VIN_1") (pintype "passive"))
      (node (ref "U2") (pin "3") (pinfunction "CE_3") (pintype "passive"))
      (node (ref "U3") (pin "1") (pinfunction "VIN_1") (pintype "passive"))
      (node (ref "U3") (pin "3") (pinfunction "CE_3") (pintype "passive"))
      (node (ref "U4") (pin "3") (pinfunction "CE_3") (pintype "passive"))
      (node (ref "U4") (pin "4") (pinfunction "VIN_4") (pintype "passive"))
      (node (ref "U5") (pin "6") (pinfunction "IN_6") (pintype "passive"))
      (node (ref "USB1") (pin "A4/B9") (pinfunction "VBUS_A4/B9") (pintype "passive"))
      (node (ref "USB1") (pin "B4/A9") (pinfunction "VBUS_B4/A9") (pintype "passive"))
    )
    (net (code "6") (name "/CC1") (class "Default")
      (node (ref "R1") (pin "2") (pinfunction "2_2") (pintype "passive"))
      (node (ref "USB1") (pin "A5") (pinfunction "CC1_A5") (pintype "passive"))
    )
    (net (code "7") (name "/CC2") (class "Default")
      (node (ref "R2") (pin "2") (pinfunction "2_2") (pintype "passive"))
      (node (ref "USB1") (pin "B5") (pinfunction "CC2_B5") (pintype "passive"))
    )
    (net (code "8") (name "/D1+") (class "Default")
      (node (ref "R5") (pin "2") (pinfunction "2_2") (pintype "passive"))
      (node (ref "USB1") (pin "A6") (pinfunction "D1+_A6") (pintype "passive"))
      (node (ref "USB1") (pin "B6") (pinfunction "D2+_B6") (pintype "passive"))
    )
    (net (code "9") (name "/D1-") (class "Default")
      (node (ref "R4") (pin "2") (pinfunction "2_2") (pintype "passive"))
      (node (ref "USB1") (pin "A7") (pinfunction "D1-_A7") (pintype "passive"))
      (node (ref "USB1") (pin "B7") (pinfunction "D2-_B7") (pintype "passive"))
    )
    (net (code "10") (name "/EH") (class "Default")
      (node (ref "USB1") (pin "13") (pinfunction "EH_13") (pintype "passive"))
      (node (ref "USB1") (pin "14") (pinfunction "EH_14") (pintype "passive"))
      (node (ref "USB1") (pin "15") (pinfunction "EH_15") (pintype "passive"))
      (node (ref "USB1") (pin "16") (pinfunction "EH_16") (pintype "passive"))
    )
    (net (code "11") (name "/FMINL") (class "Default")
      (node (ref "U1") (pin "84") (pinfunction "FMINL_84") (pintype "passive"))
    )
    (net (code "12") (name "/FMINR") (class "Default")
      (node (ref "U1") (pin "85") (pinfunction "FMINR_85") (pintype "passive"))
    )
    (net (code "13") (name "/HIPCOMFB") (class "Default")
      (node (ref "H2") (pin "1") (pinfunction "1_1") (pintype "passive"))
      (node (ref "U1") (pin "2") (pinfunction "HIPCOMFB_2") (pintype "passive"))
    )
    (net (code "14") (name "/HOSCI") (class "Default")
      (node (ref "C2") (pin "2") (pinfunction "2_2") (pintype "passive"))
      (node (ref "U1") (pin "51") (pinfunction "HOSCI_51") (pintype "passive"))
      (node (ref "X1") (pin "3") (pinfunction "OSC2_3") (pintype "passive"))
    )
    (net (code "15") (name "/HOSCO") (class "Default")
      (node (ref "C1") (pin "1") (pinfunction "1_1") (pintype "passive"))
      (node (ref "U1") (pin "52") (pinfunction "HOSCO_52") (pintype "passive"))
      (node (ref "X1") (pin "1") (pinfunction "OSC1_1") (pintype "passive"))
    )
    (net (code "16") (name "/HPCOM") (class "Default")
      (node (ref "H2") (pin "2") (pinfunction "2_2") (pintype "passive"))
      (node (ref "U1") (pin "3") (pinfunction "HPCOM_3") (pintype "passive"))
    )
    (net (code "17") (name "/HPL") (class "Default")
      (node (ref "H2") (pin "4") (pinfunction "4_4") (pintype "passive"))
      (node (ref "U1") (pin "1") (pinfunction "HPL_1") (pintype "passive"))
    )
    (net (code "18") (name "/HPR") (class "Default")
      (node (ref "H2") (pin "6") (pinfunction "6_6") (pintype "passive"))
      (node (ref "U1") (pin "88") (pinfunction "HPR_88") (pintype "passive"))
    )
    (net (code "19") (name "/LCD_CLK") (class "Default")
      (node (ref "FPC1") (pin "30") (pinfunction "30_30") (pintype "passive"))
      (node (ref "U1") (pin "26") (pinfunction "PD18_26") (pintype "passive"))
    )
    (net (code "20") (name "/LCD_D2") (class "Default")
      (node (ref "FPC1") (pin "23") (pinfunction "23_23") (pintype "passive"))
      (node (ref "U1") (pin "6") (pinfunction "PD0_6") (pintype "passive"))
    )
    (net (code "21") (name "/LCD_D3") (class "Default")
      (node (ref "FPC1") (pin "24") (pinfunction "24_24") (pintype "passive"))
      (node (ref "U1") (pin "7") (pinfunction "PD1_7") (pintype "passive"))
    )
    (net (code "22") (name "/LCD_D4") (class "Default")
      (node (ref "FPC1") (pin "25") (pinfunction "25_25") (pintype "passive"))
      (node (ref "U1") (pin "8") (pinfunction "PD2_8") (pintype "passive"))
    )
    (net (code "23") (name "/LCD_D5") (class "Default")
      (node (ref "FPC1") (pin "26") (pinfunction "26_26") (pintype "passive"))
      (node (ref "U1") (pin "9") (pinfunction "PD3_9") (pintype "passive"))
    )
    (net (code "24") (name "/LCD_D6") (class "Default")
      (node (ref "FPC1") (pin "27") (pinfunction "27_27") (pintype "passive"))
      (node (ref "U1") (pin "10") (pinfunction "PD4_10") (pintype "passive"))
    )
    (net (code "25") (name "/LCD_D7") (class "Default")
      (node (ref "FPC1") (pin "28") (pinfunction "28_28") (pintype "passive"))
      (node (ref "U1") (pin "11") (pinfunction "PD5_11") (pintype "passive"))
    )
    (net (code "26") (name "/LCD_D10") (class "Default")
      (node (ref "FPC1") (pin "15") (pinfunction "15_15") (pintype "passive"))
      (node (ref "U1") (pin "12") (pinfunction "PD6_12") (pintype "passive"))
    )
    (net (code "27") (name "/LCD_D11") (class "Default")
      (node (ref "FPC1") (pin "16") (pinfunction "16_16") (pintype "passive"))
      (node (ref "U1") (pin "13") (pinfunction "PD7_13") (pintype "passive"))
    )
    (net (code "28") (name "/LCD_D12") (class "Default")
      (node (ref "FPC1") (pin "17") (pinfunction "17_17") (pintype "passive"))
      (node (ref "U1") (pin "14") (pinfunction "PD8_14") (pintype "passive"))
    )
    (net (code "29") (name "/LCD_D13") (class "Default")
      (node (ref "FPC1") (pin "18") (pinfunction "18_18") (pintype "passive"))
      (node (ref "U1") (pin "15") (pinfunction "PD9_15") (pintype "passive"))
    )
    (net (code "30") (name "/LCD_D14") (class "Default")
      (node (ref "FPC1") (pin "19") (pinfunction "19_19") (pintype "passive"))
      (node (ref "U1") (pin "16") (pinfunction "PD10_16") (pintype "passive"))
    )
    (net (code "31") (name "/LCD_D15") (class "Default")
      (node (ref "FPC1") (pin "20") (pinfunction "20_20") (pintype "passive"))
      (node (ref "U1") (pin "17") (pinfunction "PD11_17") (pintype "passive"))
    )
    (net (code "32") (name "/LCD_D18") (class "Default")
      (node (ref "FPC1") (pin "7") (pinfunction "7_7") (pintype "passive"))
      (node (ref "U1") (pin "18") (pinfunction "PD12_18") (pintype "passive"))
    )
    (net (code "33") (name "/LCD_D19") (class "Default")
      (node (ref "FPC1") (pin "8") (pinfunction "8_8") (pintype "passive"))
      (node (ref "U1") (pin "19") (pinfunction "PD13_19") (pintype "passive"))
    )
    (net (code "34") (name "/LCD_D20") (class "Default")
      (node (ref "FPC1") (pin "9") (pinfunction "9_9") (pintype "passive"))
      (node (ref "U1") (pin "21") (pinfunction "PD14_21") (pintype "passive"))
    )
    (net (code "35") (name "/LCD_D21") (class "Default")
      (node (ref "FPC1") (pin "10") (pinfunction "10_10") (pintype "passive"))
      (node (ref "U1") (pin "23") (pinfunction "PD15_23") (pintype "passive"))
    )
    (net (code "36") (name "/LCD_D22") (class "Default")
      (node (ref "FPC1") (pin "11") (pinfunction "11_11") (pintype "passive"))
      (node (ref "U1") (pin "24") (pinfunction "PD16_24") (pintype "passive"))
    )
    (net (code "37") (name "/LCD_D23") (class "Default")
      (node (ref "FPC1") (pin "12") (pinfunction "12_12") (pintype "passive"))
      (node (ref "U1") (pin "25") (pinfunction "PD17_25") (pintype "passive"))
    )
    (net (code "38") (name "/LCD_DE") (class "Default")
      (node (ref "FPC1") (pin "34") (pinfunction "34_34") (pintype "passive"))
      (node (ref "H1") (pin "2") (pinfunction "2_2") (pintype "passive"))
      (node (ref "U1") (pin "27") (pinfunction "PD19_27") (pintype "passive"))
    )
    (net (code "39") (name "/LCD_HSYNC") (class "Default")
      (node (ref "FPC1") (pin "32") (pinfunction "32_32") (pintype "passive"))
      (node (ref "U1") (pin "28") (pinfunction "PD20_28") (pintype "passive"))
      (node (ref "U7") (pin "7") (pinfunction "PENIRQ_7") (pintype "passive"))
    )
    (net (code "40") (name "/LCD_VSYNC") (class "Default")
      (node (ref "FPC1") (pin "33") (pinfunction "33_33") (pintype "passive"))
      (node (ref "H1") (pin "1") (pinfunction "1_1") (pintype "passive"))
      (node (ref "U1") (pin "29") (pinfunction "PD21_29") (pintype "passive"))
    )
    (net (code "41") (name "/LINL") (class "Default")
      (node (ref "H2") (pin "10") (pinfunction "10_10") (pintype "passive"))
      (node (ref "U1") (pin "86") (pinfunction "LINL_86") (pintype "passive"))
    )
    (net (code "42") (name "/LRADC0") (class "Default")
      (node (ref "H2") (pin "14") (pinfunction "14_14") (pintype "passive"))
      (node (ref "U1") (pin "79") (pinfunction "LRADC0_79") (pintype "passive"))
    )
    (net (code "43") (name "/MICIN") (class "Default")
      (node (ref "H2") (pin "8") (pinfunction "8_8") (pintype "passive"))
      (node (ref "U1") (pin "87") (pinfunction "MICIN_87") (pintype "passive"))
    )
    (net (code "44") (name "/PA0") (class "Default")
      (node (ref "H2") (pin "9") (pinfunction "9_9") (pintype "passive"))
      (node (ref "U1") (pin "66") (pinfunction "TPX1_66") (pintype "passive"))
    )
    (net (code "45") (name "/PA1") (class "Default")
      (node (ref "H2") (pin "7") (pinfunction "7_7") (pintype "passive"))
      (node (ref "U1") (pin "65") (pinfunction "TPX2_65") (pintype "passive"))
    )
    (net (code "46") (name "/PA2") (class "Default")
      (node (ref "H2") (pin "5") (pinfunction "5_5") (pintype "passive"))
      (node (ref "U1") (pin "64") (pinfunction "TPY1_64") (pintype "passive"))
    )
    (net (code "47") (name "/PA3") (class "Default")
      (node (ref "H2") (pin "3") (pinfunction "3_3") (pintype "passive"))
      (node (ref "U1") (pin "63") (pinfunction "TPY2_63") (pintype "passive"))
    )
    (net (code "48") (name "/PC0") (class "Default")
      (node (ref "H1") (pin "16") (pinfunction "16_16") (pintype "passive"))
      (node (ref "U1") (pin "59") (pinfunction "PC0_59") (pintype "passive"))
      (node (ref "U8") (pin "6") (pinfunction "CLK_6") (pintype "passive"))
    )
    (net (code "49") (name "/PC1") (class "Default")
      (node (ref "H1") (pin "18") (pinfunction "18_18") (pintype "passive"))
      (node (ref "R19") (pin "1") (pinfunction "1_1") (pintype "passive"))
      (node (ref "U1") (pin "60") (pinfunction "PC1_60") (pintype "passive"))
      (node (ref "U8") (pin "1") (pinfunction "CS#_1") (pintype "passive"))
    )
    (net (code "50") (name "/PC2") (class "Default")
      (node (ref "H1") (pin "20") (pinfunction "20_20") (pintype "passive"))
      (node (ref "U1") (pin "61") (pinfunction "PC2_61") (pintype "passive"))
      (node (ref "U8") (pin "2") (pinfunction "DO_2") (pintype "passive"))
    )
    (net (code "51") (name "/PC3") (class "Default")
      (node (ref "H1") (pin "22") (pinfunction "22_22") (pintype "passive"))
      (node (ref "U1") (pin "62") (pinfunction "PC3_62") (pintype "passive"))
      (node (ref "U8") (pin "5") (pinfunction "DI_5") (pintype "passive"))
    )
    (net (code "52") (name "/PE0") (class "Default")
      (node (ref "H2") (pin "17") (pinfunction "17_17") (pintype "passive"))
      (node (ref "U1") (pin "49") (pinfunction "PE0_49") (pintype "passive"))
      (node (ref "U6") (pin "6") (pinfunction "TXD_6") (pintype "passive"))
    )
    (net (code "53") (name "/PE1") (class "Default")
      (node (ref "H2") (pin "19") (pinfunction "19_19") (pintype "passive"))
      (node (ref "U1") (pin "48") (pinfunction "PE1_48") (pintype "passive"))
      (node (ref "U6") (pin "7") (pinfunction "RXD_7") (pintype "passive"))
    )
    (net (code "54") (name "/PE2") (class "Default")
      (node (ref "H2") (pin "21") (pinfunction "21_21") (pintype "passive"))
      (node (ref "R3") (pin "1") (pinfunction "1_1") (pintype "passive"))
      (node (ref "U1") (pin "47") (pinfunction "PE2_47") (pintype "passive"))
    )
    (net (code "55") (name "/PE3") (class "Default")
      (node (ref "H1") (pin "21") (pinfunction "21_21") (pintype "passive"))
      (node (ref "U1") (pin "46") (pinfunction "PE3_46") (pintype "passive"))
    )
    (net (code "56") (name "/PE4") (class "Default")
      (node (ref "H1") (pin "19") (pinfunction "19_19") (pintype "passive"))
      (node (ref "U1") (pin "45") (pinfunction "PE4_45") (pintype "passive"))
    )
    (net (code "57") (name "/PE5") (class "Default")
      (node (ref "H1") (pin "17") (pinfunction "17_17") (pintype "passive"))
      (node (ref "U1") (pin "44") (pinfunction "PE5_44") (pintype "passive"))
    )
    (net (code "58") (name "/PE6") (class "Default")
      (node (ref "H1") (pin "15") (pinfunction "15_15") (pintype "passive"))
      (node (ref "R13") (pin "1") (pinfunction "1_1") (pintype "passive"))
      (node (ref "U1") (pin "43") (pinfunction "PE6_43") (pintype "passive"))
    )
    (net (code "59") (name "/PE7") (class "Default")
      (node (ref "H1") (pin "13") (pinfunction "13_13") (pintype "passive"))
      (node (ref "U1") (pin "42") (pinfunction "PE7_42") (pintype "passive"))
    )
    (net (code "60") (name "/PE8") (class "Default")
      (node (ref "H1") (pin "11") (pinfunction "11_11") (pintype "passive"))
      (node (ref "U1") (pin "41") (pinfunction "PE8_41") (pintype "passive"))
    )
    (net (code "61") (name "/PE9") (class "Default")
      (node (ref "H1") (pin "9") (pinfunction "9_9") (pintype "passive"))
      (node (ref "U1") (pin "40") (pinfunction "PE9_40") (pintype "passive"))
    )
    (net (code "62") (name "/PE10") (class "Default")
      (node (ref "H1") (pin "7") (pinfunction "7_7") (pintype "passive"))
      (node (ref "U1") (pin "39") (pinfunction "PE10_39") (pintype "passive"))
    )
    (net (code "63") (name "/PE11") (class "Default")
      (node (ref "H1") (pin "5") (pinfunction "5_5") (pintype "passive"))
      (node (ref "R18") (pin "2") (pinfunction "2_2") (pintype "passive"))
      (node (ref "U1") (pin "38") (pinfunction "PE11_38") (pintype "passive"))
      (node (ref "U7") (pin "10") (pinfunction "SCL_10") (pintype "passive"))
    )
    (net (code "64") (name "/PE12") (class "Default")
      (node (ref "H1") (pin "3") (pinfunction "3_3") (pintype "passive"))
      (node (ref "R17") (pin "2") (pinfunction "2_2") (pintype "passive"))
      (node (ref "U1") (pin "37") (pinfunction "PE12_37") (pintype "passive"))
      (node (ref "U7") (pin "9") (pinfunction "SDA_9") (pintype "passive"))
    )
    (net (code "65") (name "/PF0") (class "Default")
      (node (ref "H1") (pin "4") (pinfunction "4_4") (pintype "passive"))
      (node (ref "R24") (pin "1") (pinfunction "1_1") (pintype "passive"))
      (node (ref "U1") (pin "58") (pinfunction "PF0_58") (pintype "passive"))
      (node (ref "U9") (pin "8") (pinfunction "DAT1_8") (pintype "passive"))
    )
    (net (code "66") (name "/PF1") (class "Default")
      (node (ref "H1") (pin "6") (pinfunction "6_6") (pintype "passive"))
      (node (ref "R23") (pin "1") (pinfunction "1_1") (pintype "passive"))
      (node (ref "U1") (pin "57") (pinfunction "PF1_57") (pintype "passive"))
      (node (ref "U9") (pin "7") (pinfunction "DAT0_7") (pintype "passive"))
    )
    (net (code "67") (name "/PF2") (class "Default")
      (node (ref "H1") (pin "8") (pinfunction "8_8") (pintype "passive"))
      (node (ref "R25") (pin "1") (pinfunction "1_1") (pintype "passive"))
      (node (ref "U1") (pin "56") (pinfunction "PF2_56") (pintype "passive"))
    )
    (net (code "68") (name "/PF3") (class "Default")
      (node (ref "H1") (pin "10") (pinfunction "10_10") (pintype "passive"))
      (node (ref "R22") (pin "1") (pinfunction "1_1") (pintype "passive"))
      (node (ref "U1") (pin "55") (pinfunction "PF3_55") (pintype "passive"))
      (node (ref "U9") (pin "3") (pinfunction "CMD_3") (pintype "passive"))
    )
    (net (code "69") (name "/PF4") (class "Default")
      (node (ref "H1") (pin "12") (pinfunction "12_12") (pintype "passive"))
      (node (ref "R21") (pin "1") (pinfunction "1_1") (pintype "passive"))
      (node (ref "U1") (pin "54") (pinfunction "PF4_54") (pintype "passive"))
      (node (ref "U9") (pin "2") (pinfunction "CD/DAT3_2") (pintype "passive"))
    )
    (net (code "70") (name "/PF5") (class "Default")
      (node (ref "H1") (pin "14") (pinfunction "14_14") (pintype "passive"))
      (node (ref "R20") (pin "1") (pinfunction "1_1") (pintype "passive"))
      (node (ref "U1") (pin "53") (pinfunction "PF5_53") (pintype "passive"))
      (node (ref "U9") (pin "1") (pinfunction "DAT2_1") (pintype "passive"))
    )
    (net (code "71") (name "/RESET") (class "Default")
      (node (ref "C11") (pin "1") (pinfunction "1_1") (pintype "passive"))
      (node (ref "H2") (pin "12") (pinfunction "12_12") (pintype "passive"))
      (node (ref "R6") (pin "2") (pinfunction "2_2") (pintype "passive"))
      (node (ref "U1") (pin "70") (pinfunction "RESET_70") (pintype "passive"))
    )
    (net (code "72") (name "/SBU1") (class "Default")
      (node (ref "USB1") (pin "A8") (pinfunction "SBU1_A8") (pintype "passive"))
    )
    (net (code "73") (name "/SBU2") (class "Default")
      (node (ref "USB1") (pin "B8") (pinfunction "SBU2_B8") (pintype "passive"))
    )
    (net (code "74") (name "/SVREF") (class "Default")
      (node (ref "R8") (pin "2") (pinfunction "2_2") (pintype "passive"))
      (node (ref "R9") (pin "1") (pinfunction "1_1") (pintype "passive"))
      (node (ref "U1") (pin "33") (pinfunction "SVREF_33") (pintype "passive"))
    )
    (net (code "75") (name "/TVIN0") (class "Default")
      (node (ref "H4") (pin "3") (pinfunction "3_3") (pintype "passive"))
      (node (ref "U1") (pin "78") (pinfunction "TVIN0_78") (pintype "passive"))
    )
    (net (code "76") (name "/TVIN1") (class "Default")
      (node (ref "H4") (pin "4") (pinfunction "4_4") (pintype "passive"))
      (node (ref "U1") (pin "77") (pinfunction "TVIN1_77") (pintype "passive"))
    )
    (net (code "77") (name "/TVOUT") (class "Default")
      (node (ref "H2") (pin "18") (pinfunction "18_18") (pintype "passive"))
      (node (ref "U1") (pin "72") (pinfunction "TVOUT_72") (pintype "passive"))
    )
    (net (code "78") (name "/TV_VCC") (class "Default")
      (node (ref "C21") (pin "2") (pinfunction "2_2") (pintype "passive"))
      (node (ref "C22") (pin "2") (pinfunction "2_2") (pintype "passive"))
      (node (ref "R7") (pin "2") (pinfunction "2_2") (pintype "passive"))
      (node (ref "U1") (pin "73") (pinfunction "TV_VCC_73") (pintype "passive"))
    )
    (net (code "79") (name "/TV_VRN") (class "Default")
      (node (ref "C14") (pin "2") (pinfunction "2_2") (pintype "passive"))
      (node (ref "C16") (pin "2") (pinfunction "2_2") (pintype "passive"))
      (node (ref "U1") (pin "75") (pinfunction "TV_VRN_75") (pintype "passive"))
    )
    (net (code "80") (name "/TV_VRP") (class "Default")
      (node (ref "C14") (pin "1") (pinfunction "1_1") (pintype "passive"))
      (node (ref "C15") (pin "2") (pinfunction "2_2") (pintype "passive"))
      (node (ref "U1") (pin "76") (pinfunction "TV_VRP_76") (pintype "passive"))
    )
    (net (code "81") (name "/USB-DM") (class "Default")
      (node (ref "U1") (pin "68") (pinfunction "USB-DM_68") (pintype "passive"))
    )
    (net (code "82") (name "/USB-DP") (class "Default")
      (node (ref "U1") (pin "69") (pinfunction "USB-DP_69") (pintype "passive"))
    )
    (net (code "83") (name "/USB_DM") (class "Default")
      (node (ref "H2") (pin "22") (pinfunction "22_22") (pintype "passive"))
      (node (ref "R4") (pin "1") (pinfunction "1_1") (pintype "passive"))
    )
    (net (code "84") (name "/USB_DP") (class "Default")
      (node (ref "H2") (pin "20") (pinfunction "20_20") (pintype "passive"))
      (node (ref "R5") (pin "1") (pinfunction "1_1") (pintype "passive"))
    )
    (net (code "85") (name "/VRA1") (class "Default")
      (node (ref "C18") (pin "2") (pinfunction "2_2") (pintype "passive"))
      (node (ref "R11") (pin "2") (pinfunction "2_2") (pintype "passive"))
      (node (ref "U1") (pin "81") (pinfunction "VRA1_81") (pintype "passive"))
    )
    (net (code "86") (name "/VRA2") (class "Default")
      (node (ref "C17") (pin "2") (pinfunction "2_2") (pintype "passive"))
      (node (ref "R10") (pin "2") (pinfunction "2_2") (pintype "passive"))
      (node (ref "U1") (pin "83") (pinfunction "VRA2_83") (pintype "passive"))
    )
    (net (code "87") (name "/XN") (class "Default")
      (node (ref "FPC1") (pin "39") (pinfunction "39_39") (pintype "passive"))
      (node (ref "H3") (pin "3") (pinfunction "3_3") (pintype "passive"))
      (node (ref "U7") (pin "4") (pinfunction "XN_4") (pintype "passive"))
    )
    (net (code "88") (name "/XP") (class "Default")
      (node (ref "FPC1") (pin "37") (pinfunction "37_37") (pintype "passive"))
      (node (ref "H3") (pin "1") (pinfunction "1_1") (pintype "passive"))
      (node (ref "U7") (pin "2") (pinfunction "XP_2") (pintype "passive"))
    )
    (net (code "89") (name "/YN") (class "Default")
      (node (ref "FPC1") (pin "40") (pinfunction "40_40") (pintype "passive"))
      (node (ref "H3") (pin "4") (pinfunction "4_4") (pintype "passive"))
      (node (ref "U7") (pin "5") (pinfunction "YN_5") (pintype "passive"))
    )
    (net (code "90") (name "/YP") (class "Default")
      (node (ref "FPC1") (pin "38") (pinfunction "38_38") (pintype "passive"))
      (node (ref "H3") (pin "2") (pinfunction "2_2") (pintype "passive"))
      (node (ref "U7") (pin "3") (pinfunction "YP_3") (pintype "passive"))
    )
    (net (code "91") (name "GND") (class "Default")
      (node (ref "C1") (pin "2") (pinfunction "2_2") (pintype "passive"))
      (node (ref "C10") (pin "1") (pinfunction "1_1") (pintype "passive"))
      (node (ref "C11") (pin "2") (pinfunction "2_2") (pintype "passive"))
      (node (ref "C13") (pin "2") (pinfunction "2_2") (pintype "passive"))
      (node (ref "C15") (pin "1") (pinfunction "1_1") (pintype "passive"))
      (node (ref "C16") (pin "1") (pinfunction "1_1") (pintype "passive"))
      (node (ref "C17") (pin "1") (pinfunction "1_1") (pintype "passive"))
      (node (ref "C18") (pin "1") (pinfunction "1_1") (pintype "passive"))
      (node (ref "C19") (pin "1") (pinfunction "1_1") (pintype "passive"))
      (node (ref "C2") (pin "1") (pinfunction "1_1") (pintype "passive"))
      (node (ref "C20") (pin "1") (pinfunction "1_1") (pintype "passive"))
      (node (ref "C21") (pin "1") (pinfunction "1_1") (pintype "passive"))
      (node (ref "C22") (pin "1") (pinfunction "1_1") (pintype "passive"))
      (node (ref "C23") (pin "1") (pinfunction "1_1") (pintype "passive"))
      (node (ref "C24") (pin "1") (pinfunction "1_1") (pintype "passive"))
      (node (ref "C25") (pin "1") (pinfunction "1_1") (pintype "passive"))
      (node (ref "C26") (pin "1") (pinfunction "1_1") (pintype "passive"))
      (node (ref "C27") (pin "1") (pinfunction "1_1") (pintype "passive"))
      (node (ref "C28") (pin "1") (pinfunction "1_1") (pintype "passive"))
      (node (ref "C29") (pin "1") (pinfunction "1_1") (pintype "passive"))
      (node (ref "C3") (pin "1") (pinfunction "1_1") (pintype "passive"))
      (node (ref "C30") (pin "2") (pinfunction "2_2") (pintype "passive"))
      (node (ref "C31") (pin "2") (pinfunction "2_2") (pintype "passive"))
      (node (ref "C32") (pin "1") (pinfunction "1_1") (pintype "passive"))
      (node (ref "C33") (pin "2") (pinfunction "2_2") (pintype "passive"))
      (node (ref "C34") (pin "1") (pinfunction "1_1") (pintype "passive"))
      (node (ref "C4") (pin "1") (pinfunction "1_1") (pintype "passive"))
      (node (ref "C5") (pin "1") (pinfunction "1_1") (pintype "passive"))
      (node (ref "C6") (pin "1") (pinfunction "1_1") (pintype "passive"))
      (node (ref "C7") (pin "1") (pinfunction "1_1") (pintype "passive"))
      (node (ref "C8") (pin "1") (pinfunction "1_1") (pintype "passive"))
      (node (ref "C9") (pin "1") (pinfunction "1_1") (pintype "passive"))
      (node (ref "FPC1") (pin "13") (pinfunction "13_13") (pintype "passive"))
      (node (ref "FPC1") (pin "14") (pinfunction "14_14") (pintype "passive"))
      (node (ref "FPC1") (pin "21") (pinfunction "21_21") (pintype "passive"))
      (node (ref "FPC1") (pin "22") (pinfunction "22_22") (pintype "passive"))
      (node (ref "FPC1") (pin "29") (pinfunction "29_29") (pintype "passive"))
      (node (ref "FPC1") (pin "3") (pinfunction "3_3") (pintype "passive"))
      (node (ref "FPC1") (pin "36") (pinfunction "36_36") (pintype "passive"))
      (node (ref "FPC1") (pin "41") (pinfunction "41_41") (pintype "passive"))
      (node (ref "FPC1") (pin "42") (pinfunction "42_42") (pintype "passive"))
      (node (ref "FPC1") (pin "5") (pinfunction "5_5") (pintype "passive"))
      (node (ref "FPC1") (pin "6") (pinfunction "6_6") (pintype "passive"))
      (node (ref "H2") (pin "13") (pinfunction "13_13") (pintype "passive"))
      (node (ref "LDO1") (pin "2") (pinfunction "VSS_2") (pintype "passive"))
      (node (ref "R1") (pin "1") (pinfunction "1_1") (pintype "passive"))
      (node (ref "R10") (pin "1") (pinfunction "1_1") (pintype "passive"))
      (node (ref "R11") (pin "1") (pinfunction "1_1") (pintype "passive"))
      (node (ref "R14") (pin "1") (pinfunction "1_1") (pintype "passive"))
      (node (ref "R15") (pin "1") (pinfunction "1_1") (pintype "passive"))
      (node (ref "R16") (pin "1") (pinfunction "1_1") (pintype "passive"))
      (node (ref "R2") (pin "1") (pinfunction "1_1") (pintype "passive"))
      (node (ref "R9") (pin "2") (pinfunction "2_2") (pintype "passive"))
      (node (ref "U1") (pin "74") (pinfunction "TVGND_74") (pintype "passive"))
      (node (ref "U1") (pin "82") (pinfunction "AGND_82") (pintype "passive"))
      (node (ref "U1") (pin "89") (pinfunction "GND_89") (pintype "passive"))
      (node (ref "U2") (pin "2") (pinfunction "VSS_2") (pintype "passive"))
      (node (ref "U3") (pin "2") (pinfunction "VSS_2") (pintype "passive"))
      (node (ref "U4") (pin "2") (pinfunction "VSS_2") (pintype "passive"))
      (node (ref "U5") (pin "2") (pinfunction "GND_2") (pintype "passive"))
      (node (ref "U6") (pin "3") (pinfunction "GND_3") (pintype "passive"))
      (node (ref "U7") (pin "6") (pinfunction "GND_6") (pintype "passive"))
      (node (ref "U7") (pin "8") (pinfunction "A0_8") (pintype "passive"))
      (node (ref "U8") (pin "4") (pinfunction "GND_4") (pintype "passive"))
      (node (ref "U9") (pin "10") (pinfunction "10_10") (pintype "passive"))
      (node (ref "U9") (pin "11") (pinfunction "11_11") (pintype "passive"))
      (node (ref "U9") (pin "12") (pinfunction "12_12") (pintype "passive"))
      (node (ref "U9") (pin "13") (pinfunction "13_13") (pintype "passive"))
      (node (ref "U9") (pin "6") (pinfunction "VSS_6") (pintype "passive"))
      (node (ref "USB1") (pin "A1/B12") (pinfunction "GND_A1/B12") (pintype "passive"))
      (node (ref "USB1") (pin "B1/A12") (pinfunction "GND_B1/A12") (pintype "passive"))
      (node (ref "USB2") (pin "A1/B12") (pinfunction "GND_A1/B12") (pintype "passive"))
      (node (ref "USB2") (pin "B1/A12") (pinfunction "GND_B1/A12") (pintype "passive"))
      (node (ref "X1") (pin "2") (pinfunction "GND_2") (pintype "passive"))
      (node (ref "X1") (pin "4") (pinfunction "GND_4") (pintype "passive"))
    )
    (net (code "92") (name "Net-(C12-Pad2)") (class "Default")
      (node (ref "C12") (pin "2") (pinfunction "2_2") (pintype "passive"))
      (node (ref "C13") (pin "1") (pinfunction "1_1") (pintype "passive"))
    )
    (net (code "93") (name "Net-(D1-K)") (class "Default")
      (node (ref "D1") (pin "1") (pinfunction "K_1") (pintype "passive"))
      (node (ref "U5") (pin "5") (pinfunction "OV_5") (pintype "passive"))
    )
    (net (code "94") (name "Net-(D2-K)") (class "Default")
      (node (ref "D2") (pin "1") (pinfunction "K_1") (pintype "passive"))
      (node (ref "D3") (pin "1") (pinfunction "K_1") (pintype "passive"))
    )
    (net (code "95") (name "Net-(D3-A)") (class "Default")
      (node (ref "D3") (pin "2") (pinfunction "A_2") (pintype "passive"))
      (node (ref "USB2") (pin "A4/B9") (pinfunction "VBUS_A4/B9") (pintype "passive"))
    )
    (net (code "96") (name "Net-(U5-EN)") (class "Default")
      (node (ref "R12") (pin "2") (pinfunction "2_2") (pintype "passive"))
      (node (ref "R13") (pin "2") (pinfunction "2_2") (pintype "passive"))
      (node (ref "U5") (pin "4") (pinfunction "EN_4") (pintype "passive"))
    )
    (net (code "97") (name "Net-(U6-UD+)") (class "Default")
      (node (ref "U6") (pin "1") (pinfunction "UD+_1") (pintype "passive"))
      (node (ref "USB2") (pin "A6") (pinfunction "D1+_A6") (pintype "passive"))
      (node (ref "USB2") (pin "B6") (pinfunction "D2+_B6") (pintype "passive"))
    )
    (net (code "98") (name "Net-(U6-UD-)") (class "Default")
      (node (ref "U6") (pin "2") (pinfunction "UD-_2") (pintype "passive"))
      (node (ref "USB2") (pin "A7") (pinfunction "D1-_A7") (pintype "passive"))
      (node (ref "USB2") (pin "B7") (pinfunction "D2-_B7") (pintype "passive"))
    )
    (net (code "99") (name "Net-(U9-CLK)") (class "Default")
      (node (ref "R25") (pin "2") (pinfunction "2_2") (pintype "passive"))
      (node (ref "U9") (pin "5") (pinfunction "CLK_5") (pintype "passive"))
    )
    (net (code "100") (name "Net-(USB2-CC1)") (class "Default")
      (node (ref "R15") (pin "2") (pinfunction "2_2") (pintype "passive"))
      (node (ref "USB2") (pin "A5") (pinfunction "CC1_A5") (pintype "passive"))
    )
    (net (code "101") (name "Net-(USB2-CC2)") (class "Default")
      (node (ref "R16") (pin "2") (pinfunction "2_2") (pintype "passive"))
      (node (ref "USB2") (pin "B5") (pinfunction "CC2_B5") (pintype "passive"))
    )
    (net (code "102") (name "VLED+") (class "Default")
      (node (ref "C30") (pin "1") (pinfunction "1_1") (pintype "passive"))
      (node (ref "C31") (pin "1") (pinfunction "1_1") (pintype "passive"))
      (node (ref "D1") (pin "2") (pinfunction "A_2") (pintype "passive"))
      (node (ref "FPC1") (pin "1") (pinfunction "1_1") (pintype "passive"))
      (node (ref "H4") (pin "1") (pinfunction "1_1") (pintype "passive"))
      (node (ref "L1") (pin "1") (pinfunction "1_1") (pintype "passive"))
    )
    (net (code "103") (name "VLED-") (class "Default")
      (node (ref "FPC1") (pin "2") (pinfunction "2_2") (pintype "passive"))
      (node (ref "H4") (pin "2") (pinfunction "2_2") (pintype "passive"))
      (node (ref "R14") (pin "2") (pinfunction "2_2") (pintype "passive"))
      (node (ref "U5") (pin "3") (pinfunction "FB_3") (pintype "passive"))
    )
    (net (code "104") (name "unconnected-(FPC1-Pad35)") (class "Default")
      (node (ref "FPC1") (pin "35") (pinfunction "35_35") (pintype "passive"))
    )
    (net (code "105") (name "unconnected-(LDO1-NC-Pad4)") (class "Default")
      (node (ref "LDO1") (pin "4") (pinfunction "NC_4") (pintype "passive"))
    )
    (net (code "106") (name "unconnected-(U2-NC-Pad4)") (class "Default")
      (node (ref "U2") (pin "4") (pinfunction "NC_4") (pintype "passive"))
    )
    (net (code "107") (name "unconnected-(U3-NC-Pad4)") (class "Default")
      (node (ref "U3") (pin "4") (pinfunction "NC_4") (pintype "passive"))
    )
    (net (code "108") (name "unconnected-(U4-NC-Pad5)") (class "Default")
      (node (ref "U4") (pin "5") (pinfunction "NC_5") (pintype "passive"))
    )
    (net (code "109") (name "unconnected-(U5-SW-Pad1)") (class "Default")
      (node (ref "U5") (pin "1") (pinfunction "SW_1") (pintype "passive"))
    )
    (net (code "110") (name "unconnected-(U6-RTS#-Pad4)") (class "Default")
      (node (ref "U6") (pin "4") (pinfunction "RTS#_4") (pintype "passive"))
    )
    (net (code "111") (name "unconnected-(U9-SWITCH-Pad9)") (class "Default")
      (node (ref "U9") (pin "9") (pinfunction "SWITCH_9") (pintype "passive"))
    )
    (net (code "112") (name "unconnected-(USB2-EH-Pad13)") (class "Default")
      (node (ref "USB2") (pin "13") (pinfunction "EH_13") (pintype "passive"))
    )
    (net (code "113") (name "unconnected-(USB2-EH-Pad14)") (class "Default")
      (node (ref "USB2") (pin "14") (pinfunction "EH_14") (pintype "passive"))
    )
    (net (code "114") (name "unconnected-(USB2-EH-Pad15)") (class "Default")
      (node (ref "USB2") (pin "15") (pinfunction "EH_15") (pintype "passive"))
    )
    (net (code "115") (name "unconnected-(USB2-EH-Pad16)") (class "Default")
      (node (ref "USB2") (pin "16") (pinfunction "EH_16") (pintype "passive"))
    )
    (net (code "116") (name "unconnected-(USB2-SBU1-PadA8)") (class "Default")
      (node (ref "USB2") (pin "A8") (pinfunction "SBU1_A8") (pintype "passive"))
    )
    (net (code "117") (name "unconnected-(USB2-SBU2-PadB8)") (class "Default")
      (node (ref "USB2") (pin "B8") (pinfunction "SBU2_B8") (pintype "passive"))
    )
    (net (code "118") (name "unconnected-(USB2-VBUS-PadB4{slash}A9)") (class "Default")
      (node (ref "USB2") (pin "B4/A9") (pinfunction "VBUS_B4/A9") (pintype "passive"))
    )
  )
)
